# dyno_revA.net
KiCad netlist of a schematic drawn in EAGLE
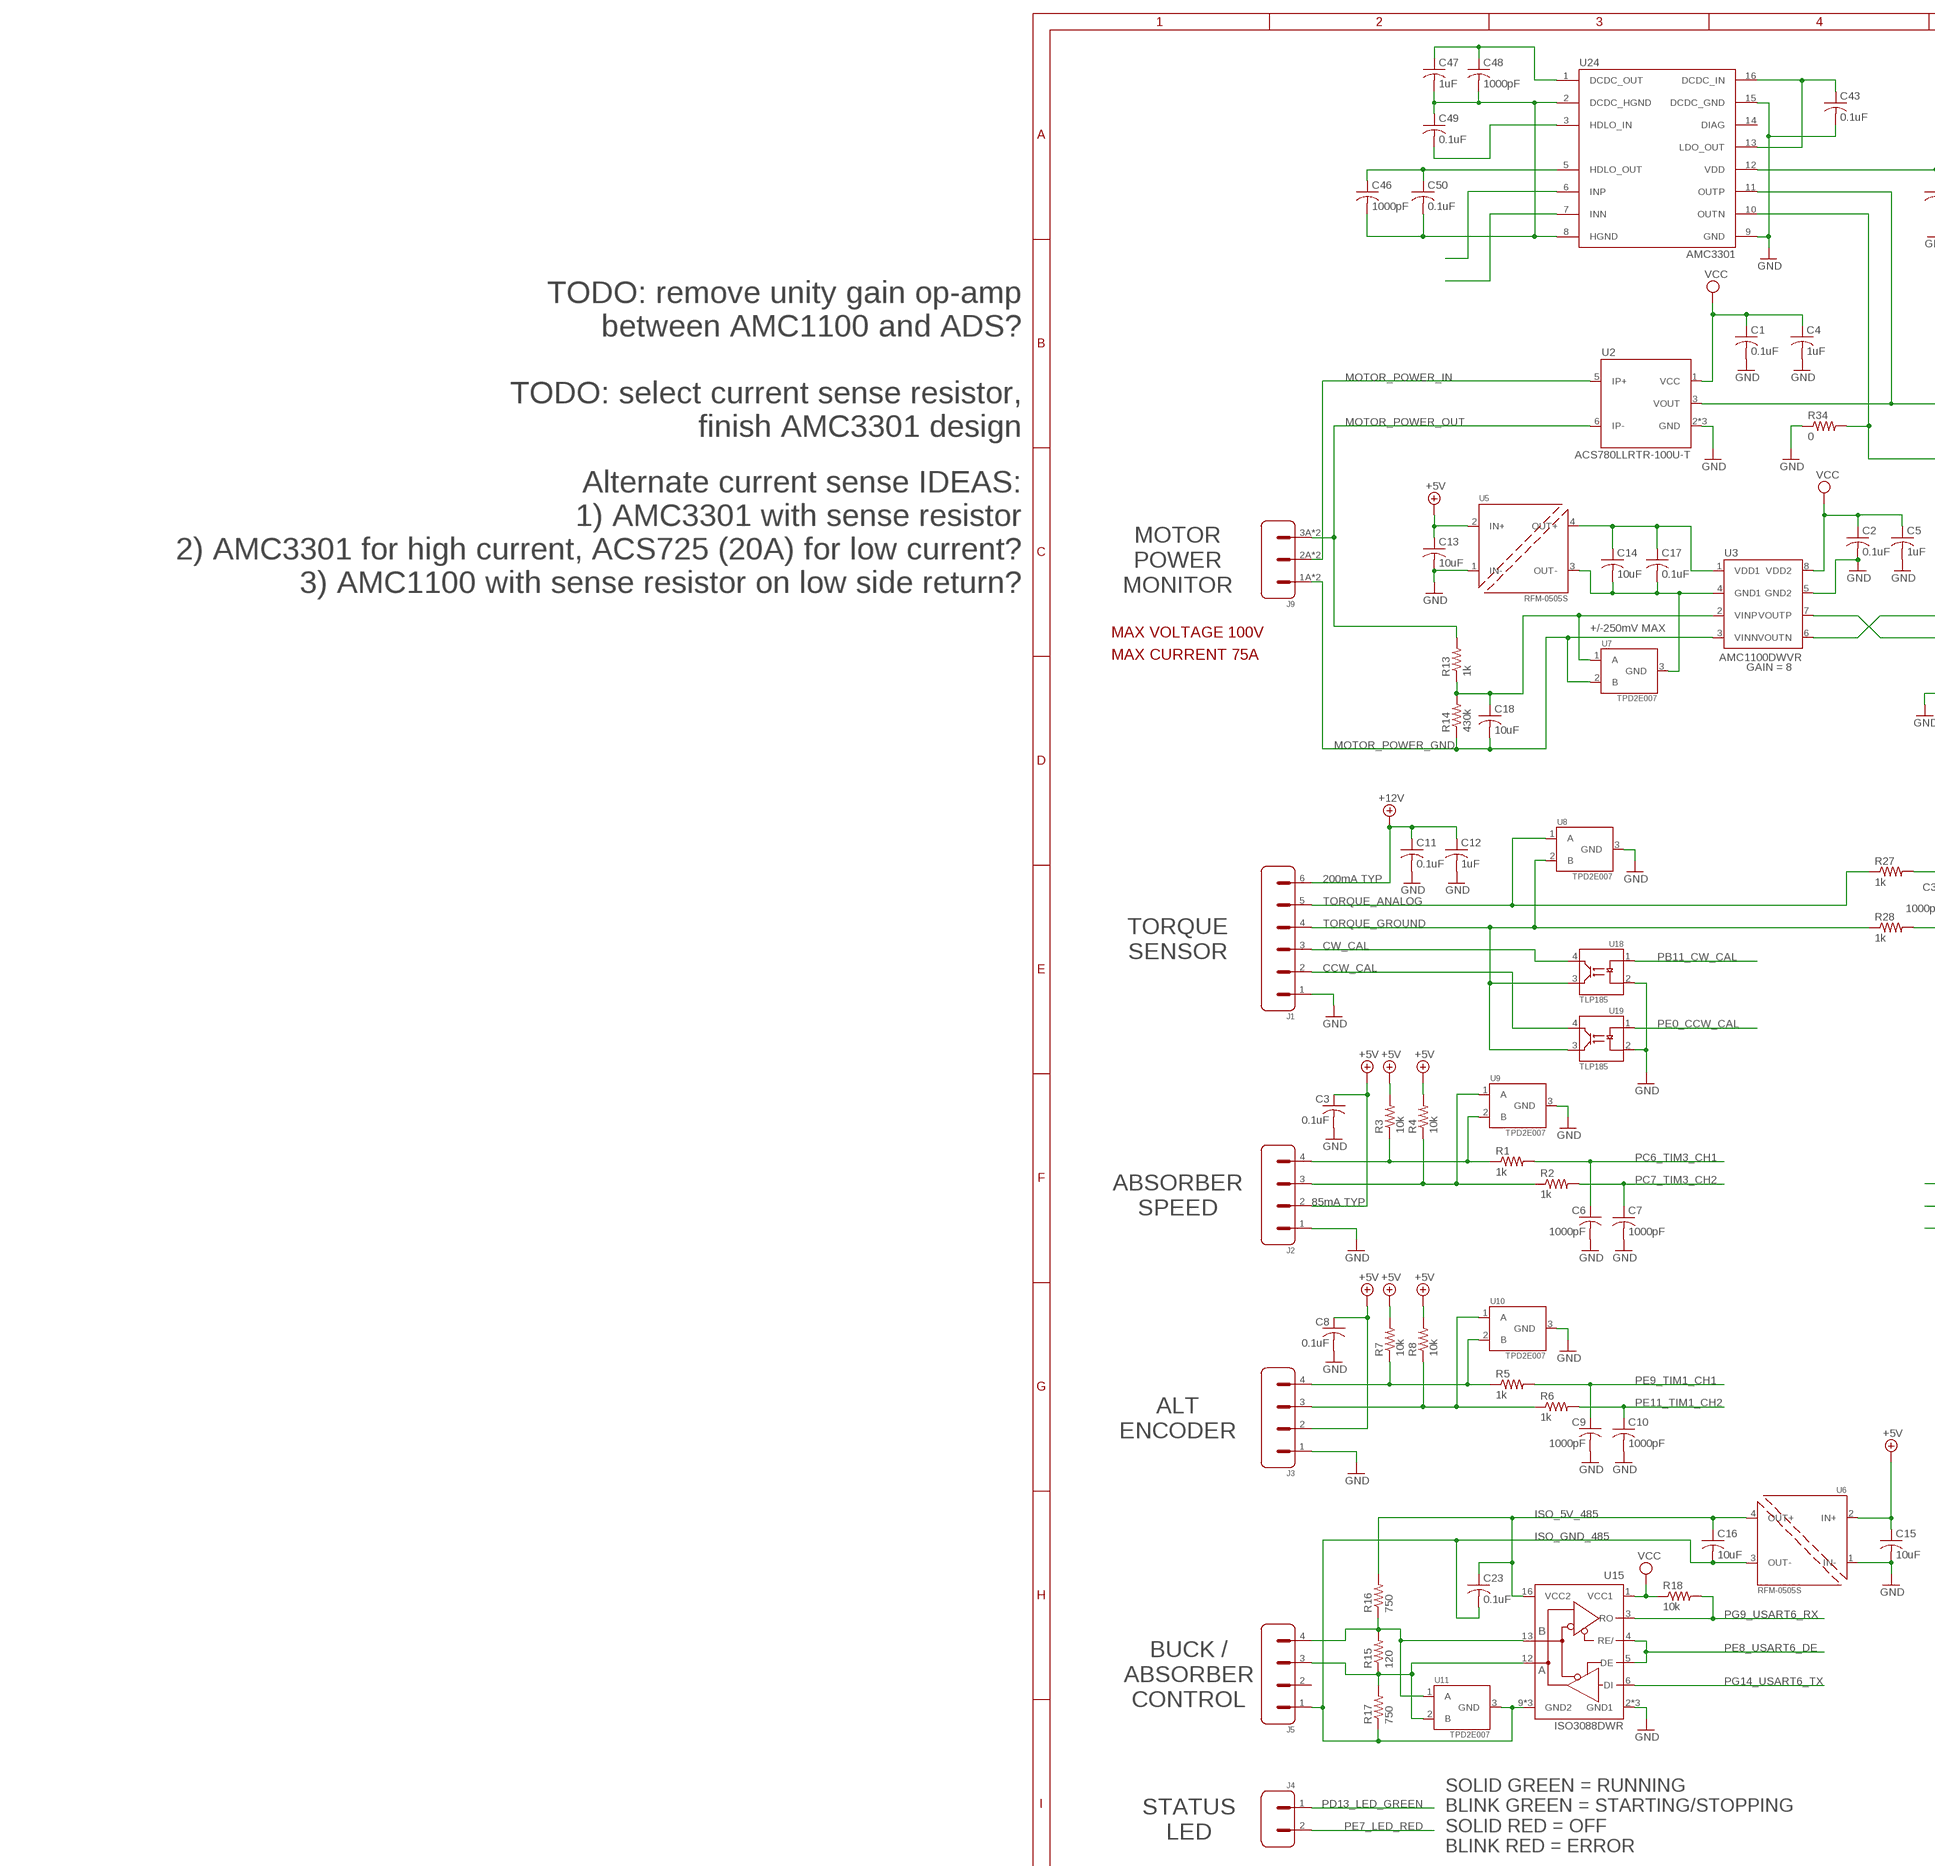
[diagram p0: schematic, sheet 1, part 1 of 2]
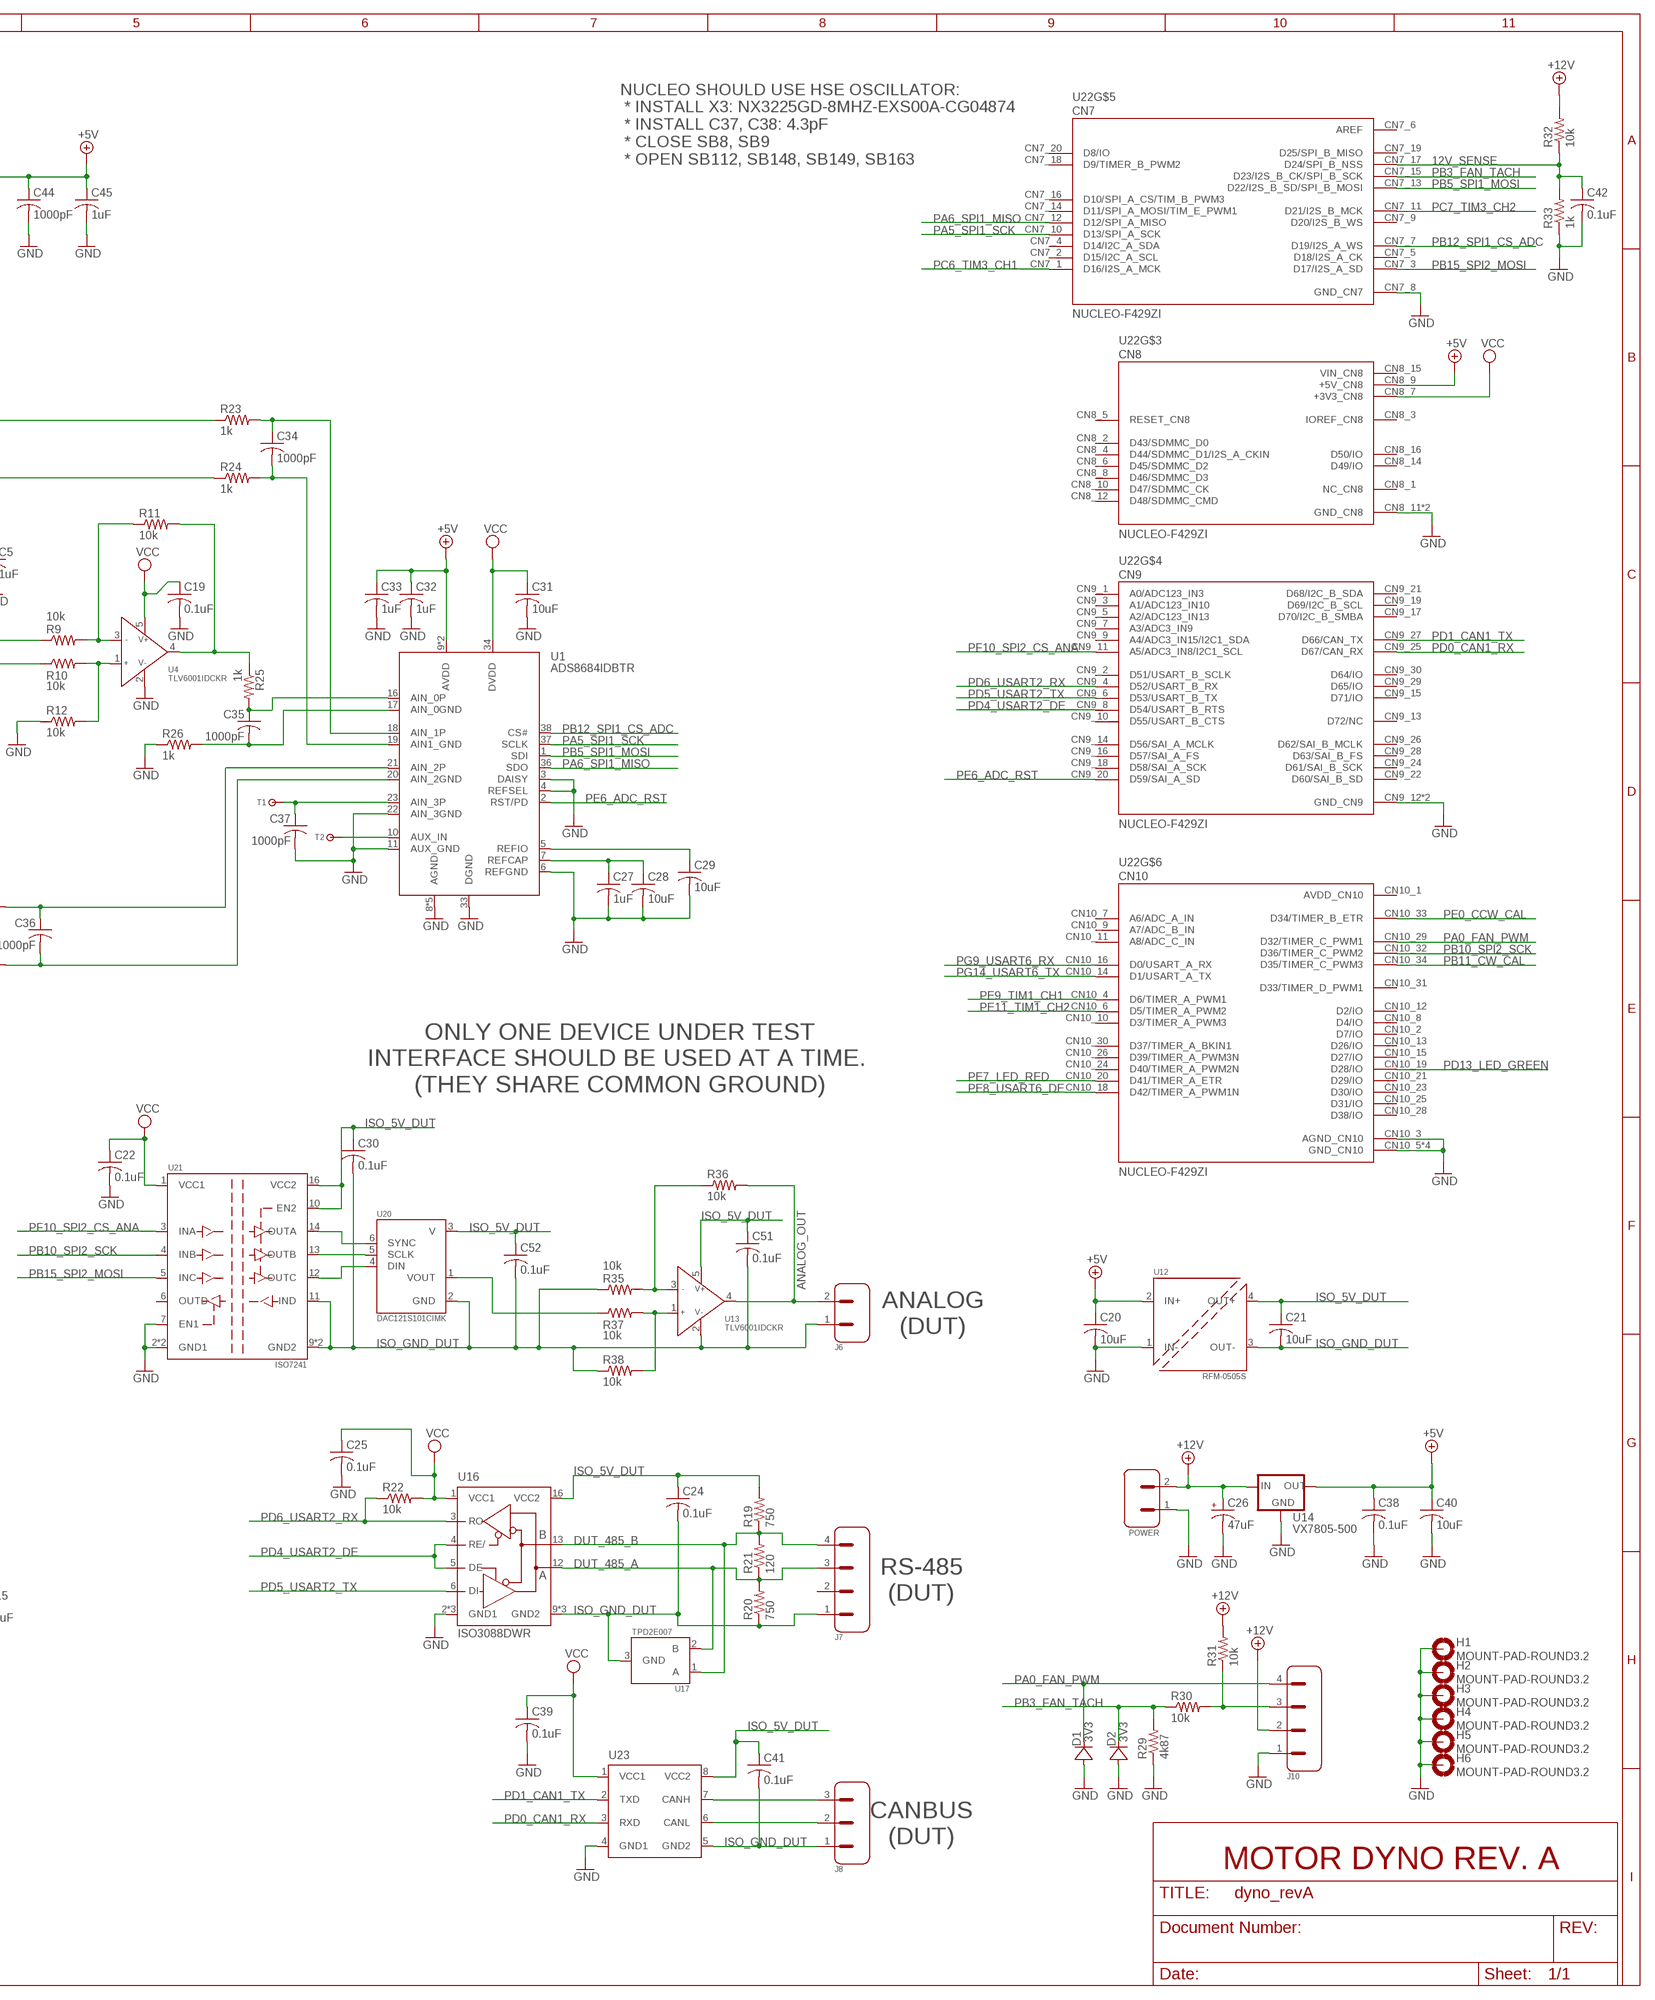
[diagram p1: schematic, sheet 1, part 2 of 2]

(export (version "E")
  (design (tool "Eeschema 10.0.6"))
  (components
    (comp (ref "C1")
      (value "0.1uF")
      (footprint "eagle-import:CAPC1608X90(C0603)")
      (fields (field (name "VOLTAGE") "50V"))
      (libsource (lib "eagle-import") (part "CL10B104KB8NNNC"))
    )
    (comp (ref "C2")
      (value "0.1uF")
      (footprint "eagle-import:CAPC1608X90(C0603)")
      (fields (field (name "VOLTAGE") "50V"))
      (libsource (lib "eagle-import") (part "CL10B104KB8NNNC"))
    )
    (comp (ref "C3")
      (value "0.1uF")
      (footprint "eagle-import:CAPC1608X90(C0603)")
      (fields (field (name "VOLTAGE") "50V"))
      (libsource (lib "eagle-import") (part "CL10B104KB8NNNC"))
    )
    (comp (ref "C4")
      (value "1uF")
      (footprint "eagle-import:CAPC1608X90(C0603)")
      (fields (field (name "VOLTAGE") "50V"))
      (libsource (lib "eagle-import") (part "CL10A105KB8NNNC"))
    )
    (comp (ref "C5")
      (value "1uF")
      (footprint "eagle-import:CAPC1608X90(C0603)")
      (fields (field (name "VOLTAGE") "50V"))
      (libsource (lib "eagle-import") (part "CL10A105KB8NNNC"))
    )
    (comp (ref "C6")
      (value "1000pF")
      (footprint "eagle-import:CAPC1608X90(C0603)")
      (fields (field (name "VOLTAGE") "50V"))
      (libsource (lib "eagle-import") (part "CL10B102KB8NNNC"))
    )
    (comp (ref "C7")
      (value "1000pF")
      (footprint "eagle-import:CAPC1608X90(C0603)")
      (fields (field (name "VOLTAGE") "50V"))
      (libsource (lib "eagle-import") (part "CL10B102KB8NNNC"))
    )
    (comp (ref "C8")
      (value "0.1uF")
      (footprint "eagle-import:CAPC1608X90(C0603)")
      (fields (field (name "VOLTAGE") "50V"))
      (libsource (lib "eagle-import") (part "CL10B104KB8NNNC"))
    )
    (comp (ref "C9")
      (value "1000pF")
      (footprint "eagle-import:CAPC1608X90(C0603)")
      (fields (field (name "VOLTAGE") "50V"))
      (libsource (lib "eagle-import") (part "CL10B102KB8NNNC"))
    )
    (comp (ref "C10")
      (value "1000pF")
      (footprint "eagle-import:CAPC1608X90(C0603)")
      (fields (field (name "VOLTAGE") "50V"))
      (libsource (lib "eagle-import") (part "CL10B102KB8NNNC"))
    )
    (comp (ref "C11")
      (value "0.1uF")
      (footprint "eagle-import:CAPC1608X90(C0603)")
      (fields (field (name "VOLTAGE") "50V"))
      (libsource (lib "eagle-import") (part "CL10B104KB8NNNC"))
    )
    (comp (ref "C12")
      (value "1uF")
      (footprint "eagle-import:CAPC1608X90(C0603)")
      (fields (field (name "VOLTAGE") "50V"))
      (libsource (lib "eagle-import") (part "CL10A105KB8NNNC"))
    )
    (comp (ref "C13")
      (value "10uF")
      (footprint "eagle-import:CAPC2012X145")
      (fields (field (name "VOLTAGE") "25V"))
      (libsource (lib "eagle-import") (part "CL21A106KAYNNNE"))
    )
    (comp (ref "C14")
      (value "10uF")
      (footprint "eagle-import:CAPC2012X145")
      (fields (field (name "VOLTAGE") "25V"))
      (libsource (lib "eagle-import") (part "CL21A106KAYNNNE"))
    )
    (comp (ref "C15")
      (value "10uF")
      (footprint "eagle-import:CAPC2012X145")
      (fields (field (name "VOLTAGE") "25V"))
      (libsource (lib "eagle-import") (part "CL21A106KAYNNNE"))
    )
    (comp (ref "C16")
      (value "10uF")
      (footprint "eagle-import:CAPC2012X145")
      (fields (field (name "VOLTAGE") "25V"))
      (libsource (lib "eagle-import") (part "CL21A106KAYNNNE"))
    )
    (comp (ref "C17")
      (value "0.1uF")
      (footprint "eagle-import:CAPC1608X90(C0603)")
      (fields (field (name "VOLTAGE") "50V"))
      (libsource (lib "eagle-import") (part "CL10B104KB8NNNC"))
    )
    (comp (ref "C18")
      (value "10uF")
      (footprint "eagle-import:CAPC2012X145")
      (fields (field (name "VOLTAGE") "25V"))
      (libsource (lib "eagle-import") (part "CL21A106KAYNNNE"))
    )
    (comp (ref "C19")
      (value "0.1uF")
      (footprint "eagle-import:CAPC1608X90(C0603)")
      (fields (field (name "VOLTAGE") "50V"))
      (libsource (lib "eagle-import") (part "CL10B104KB8NNNC"))
    )
    (comp (ref "C20")
      (value "10uF")
      (footprint "eagle-import:CAPC2012X145")
      (fields (field (name "VOLTAGE") "25V"))
      (libsource (lib "eagle-import") (part "CL21A106KAYNNNE"))
    )
    (comp (ref "C21")
      (value "10uF")
      (footprint "eagle-import:CAPC2012X145")
      (fields (field (name "VOLTAGE") "25V"))
      (libsource (lib "eagle-import") (part "CL21A106KAYNNNE"))
    )
    (comp (ref "C22")
      (value "0.1uF")
      (footprint "eagle-import:CAPC1608X90(C0603)")
      (fields (field (name "VOLTAGE") "50V"))
      (libsource (lib "eagle-import") (part "CL10B104KB8NNNC"))
    )
    (comp (ref "C23")
      (value "0.1uF")
      (footprint "eagle-import:CAPC1608X90(C0603)")
      (fields (field (name "VOLTAGE") "50V"))
      (libsource (lib "eagle-import") (part "CL10B104KB8NNNC"))
    )
    (comp (ref "C24")
      (value "0.1uF")
      (footprint "eagle-import:CAPC1608X90(C0603)")
      (fields (field (name "VOLTAGE") "50V"))
      (libsource (lib "eagle-import") (part "CL10B104KB8NNNC"))
    )
    (comp (ref "C25")
      (value "0.1uF")
      (footprint "eagle-import:CAPC1608X90(C0603)")
      (fields (field (name "VOLTAGE") "50V"))
      (libsource (lib "eagle-import") (part "CL10B104KB8NNNC"))
    )
    (comp (ref "C26")
      (value "47uF")
      (footprint "eagle-import:CAPAE830X850(PANA_F)")
      (libsource (lib "eagle-import") (part "HHXA500ARA470MHA0G"))
    )
    (comp (ref "C27")
      (value "1uF")
      (footprint "eagle-import:CAPC1608X90(C0603)")
      (fields (field (name "VOLTAGE") "50V"))
      (libsource (lib "eagle-import") (part "CL10A105KB8NNNC"))
    )
    (comp (ref "C28")
      (value "10uF")
      (footprint "eagle-import:CAPC1608X90(C0603)")
      (fields (field (name "VOLTAGE") "6.3V"))
      (libsource (lib "eagle-import") (part "CL10A106KQ8NNNC"))
    )
    (comp (ref "C29")
      (value "10uF")
      (footprint "eagle-import:CAPC1608X90(C0603)")
      (fields (field (name "VOLTAGE") "6.3V"))
      (libsource (lib "eagle-import") (part "CL10A106KQ8NNNC"))
    )
    (comp (ref "C30")
      (value "0.1uF")
      (footprint "eagle-import:CAPC1608X90(C0603)")
      (fields (field (name "VOLTAGE") "50V"))
      (libsource (lib "eagle-import") (part "CL10B104KB8NNNC"))
    )
    (comp (ref "C31")
      (value "10uF")
      (footprint "eagle-import:CAPC1608X90(C0603)")
      (fields (field (name "VOLTAGE") "6.3V"))
      (libsource (lib "eagle-import") (part "CL10A106KQ8NNNC"))
    )
    (comp (ref "C32")
      (value "1uF")
      (footprint "eagle-import:CAPC1608X90(C0603)")
      (fields (field (name "VOLTAGE") "50V"))
      (libsource (lib "eagle-import") (part "CL10A105KB8NNNC"))
    )
    (comp (ref "C33")
      (value "1uF")
      (footprint "eagle-import:CAPC1608X90(C0603)")
      (fields (field (name "VOLTAGE") "50V"))
      (libsource (lib "eagle-import") (part "CL10A105KB8NNNC"))
    )
    (comp (ref "C34")
      (value "1000pF")
      (footprint "eagle-import:CAPC1608X90(C0603)")
      (fields (field (name "VOLTAGE") "50V"))
      (libsource (lib "eagle-import") (part "CL10B102KB8NNNC"))
    )
    (comp (ref "C35")
      (value "1000pF")
      (footprint "eagle-import:CAPC1608X90(C0603)")
      (fields (field (name "VOLTAGE") "50V"))
      (libsource (lib "eagle-import") (part "CL10B102KB8NNNC"))
    )
    (comp (ref "C36")
      (value "1000pF")
      (footprint "eagle-import:CAPC1608X90(C0603)")
      (fields (field (name "VOLTAGE") "50V"))
      (libsource (lib "eagle-import") (part "CL10B102KB8NNNC"))
    )
    (comp (ref "C37")
      (value "1000pF")
      (footprint "eagle-import:CAPC1608X90(C0603)")
      (fields (field (name "VOLTAGE") "50V"))
      (libsource (lib "eagle-import") (part "CL10B102KB8NNNC"))
    )
    (comp (ref "C38")
      (value "0.1uF")
      (footprint "eagle-import:CAPC1608X90(C0603)")
      (fields (field (name "VOLTAGE") "50V"))
      (libsource (lib "eagle-import") (part "CL10B104KB8NNNC"))
    )
    (comp (ref "C39")
      (value "0.1uF")
      (footprint "eagle-import:CAPC1608X90(C0603)")
      (fields (field (name "VOLTAGE") "50V"))
      (libsource (lib "eagle-import") (part "CL10B104KB8NNNC"))
    )
    (comp (ref "C40")
      (value "10uF")
      (footprint "eagle-import:CAPC2012X145")
      (fields (field (name "VOLTAGE") "25V"))
      (libsource (lib "eagle-import") (part "CL21A106KAYNNNE"))
    )
    (comp (ref "C41")
      (value "0.1uF")
      (footprint "eagle-import:CAPC1608X90(C0603)")
      (fields (field (name "VOLTAGE") "50V"))
      (libsource (lib "eagle-import") (part "CL10B104KB8NNNC"))
    )
    (comp (ref "C42")
      (value "0.1uF")
      (footprint "eagle-import:CAPC1608X90(C0603)")
      (fields (field (name "VOLTAGE") "50V"))
      (libsource (lib "eagle-import") (part "CL10B104KB8NNNC"))
    )
    (comp (ref "C43")
      (value "0.1uF")
      (footprint "eagle-import:CAPC1608X90(C0603)")
      (fields (field (name "VOLTAGE") "50V"))
      (libsource (lib "eagle-import") (part "CL10B104KB8NNNC"))
    )
    (comp (ref "C44")
      (value "1000pF")
      (footprint "eagle-import:CAPC1608X90(C0603)")
      (fields (field (name "VOLTAGE") "50V"))
      (libsource (lib "eagle-import") (part "CL10B102KB8NNNC"))
    )
    (comp (ref "C45")
      (value "1uF")
      (footprint "eagle-import:CAPC1608X90(C0603)")
      (fields (field (name "VOLTAGE") "50V"))
      (libsource (lib "eagle-import") (part "CL10A105KB8NNNC"))
    )
    (comp (ref "C46")
      (value "1000pF")
      (footprint "eagle-import:CAPC1608X90(C0603)")
      (fields (field (name "VOLTAGE") "50V"))
      (libsource (lib "eagle-import") (part "CL10B102KB8NNNC"))
    )
    (comp (ref "C47")
      (value "1uF")
      (footprint "eagle-import:CAPC1608X90(C0603)")
      (fields (field (name "VOLTAGE") "50V"))
      (libsource (lib "eagle-import") (part "CL10A105KB8NNNC"))
    )
    (comp (ref "C48")
      (value "1000pF")
      (footprint "eagle-import:CAPC1608X90(C0603)")
      (fields (field (name "VOLTAGE") "50V"))
      (libsource (lib "eagle-import") (part "CL10B102KB8NNNC"))
    )
    (comp (ref "C49")
      (value "0.1uF")
      (footprint "eagle-import:CAPC1608X90(C0603)")
      (fields (field (name "VOLTAGE") "50V"))
      (libsource (lib "eagle-import") (part "CL10B104KB8NNNC"))
    )
    (comp (ref "C50")
      (value "0.1uF")
      (footprint "eagle-import:CAPC1608X90(C0603)")
      (fields (field (name "VOLTAGE") "50V"))
      (libsource (lib "eagle-import") (part "CL10B104KB8NNNC"))
    )
    (comp (ref "C51")
      (value "0.1uF")
      (footprint "eagle-import:CAPC1608X90(C0603)")
      (fields (field (name "VOLTAGE") "50V"))
      (libsource (lib "eagle-import") (part "CL10B104KB8NNNC"))
    )
    (comp (ref "C52")
      (value "0.1uF")
      (footprint "eagle-import:CAPC1608X90(C0603)")
      (fields (field (name "VOLTAGE") "50V"))
      (libsource (lib "eagle-import") (part "CL10B104KB8NNNC"))
    )
    (comp (ref "D1")
      (value "3V3")
      (footprint "eagle-import:SOD2513X110(SOD323)")
      (libsource (lib "eagle-import") (part "D1213A-01WS-7"))
    )
    (comp (ref "D2")
      (value "3V3")
      (footprint "eagle-import:SOD2513X110(SOD323)")
      (libsource (lib "eagle-import") (part "D1213A-01WS-7"))
    )
    (comp (ref "H1")
      (value "MOUNT-PAD-ROUND3.2")
      (footprint "eagle-import:3,2-PAD")
      (libsource (lib "eagle-import") (part "MOUNT-PAD-ROUND3.2"))
    )
    (comp (ref "H2")
      (value "MOUNT-PAD-ROUND3.2")
      (footprint "eagle-import:3,2-PAD")
      (libsource (lib "eagle-import") (part "MOUNT-PAD-ROUND3.2"))
    )
    (comp (ref "H3")
      (value "MOUNT-PAD-ROUND3.2")
      (footprint "eagle-import:3,2-PAD")
      (libsource (lib "eagle-import") (part "MOUNT-PAD-ROUND3.2"))
    )
    (comp (ref "H4")
      (value "MOUNT-PAD-ROUND3.2")
      (footprint "eagle-import:3,2-PAD")
      (libsource (lib "eagle-import") (part "MOUNT-PAD-ROUND3.2"))
    )
    (comp (ref "H5")
      (value "MOUNT-PAD-ROUND3.2")
      (footprint "eagle-import:3,2-PAD")
      (libsource (lib "eagle-import") (part "MOUNT-PAD-ROUND3.2"))
    )
    (comp (ref "H6")
      (value "MOUNT-PAD-ROUND3.2")
      (footprint "eagle-import:3,2-PAD")
      (libsource (lib "eagle-import") (part "MOUNT-PAD-ROUND3.2"))
    )
    (comp (ref "J1")
      (value "502584-0670")
      (footprint "eagle-import:502584-0670")
      (libsource (lib "eagle-import") (part "502584-0670"))
    )
    (comp (ref "J2")
      (value "502584-0470")
      (footprint "eagle-import:502584-0470")
      (libsource (lib "eagle-import") (part "502584-0470"))
    )
    (comp (ref "J3")
      (value "502584-0470")
      (footprint "eagle-import:502584-0470")
      (libsource (lib "eagle-import") (part "502584-0470"))
    )
    (comp (ref "J4")
      (value "502584-0270")
      (footprint "eagle-import:502584-0270")
      (libsource (lib "eagle-import") (part "502584-0270"))
    )
    (comp (ref "J5")
      (value "43650-0416")
      (footprint "eagle-import:43650-0416")
      (libsource (lib "eagle-import") (part "43650-0416"))
    )
    (comp (ref "J6")
      (value "502584-0270")
      (footprint "eagle-import:502584-0270")
      (libsource (lib "eagle-import") (part "502584-0270"))
    )
    (comp (ref "J7")
      (value "43650-0416")
      (footprint "eagle-import:43650-0416")
      (libsource (lib "eagle-import") (part "43650-0416"))
    )
    (comp (ref "J8")
      (value "43650-0316")
      (footprint "eagle-import:43650-0316")
      (libsource (lib "eagle-import") (part "43650-0316"))
    )
    (comp (ref "J9")
      (value "1017532")
      (footprint "eagle-import:1017532")
      (libsource (lib "eagle-import") (part "1017532"))
    )
    (comp (ref "J10")
      (value "22-23-2041")
      (footprint "eagle-import:22-23-2041")
      (libsource (lib "eagle-import") (part "22-23-2041"))
    )
    (comp (ref "POWER")
      (value "39-29-0023")
      (footprint "eagle-import:5566-2")
      (libsource (lib "eagle-import") (part "39-29-0023"))
    )
    (comp (ref "R1")
      (value "1k")
      (footprint "eagle-import:RESC1608X55(ERJ-0603)")
      (libsource (lib "eagle-import") (part "ERJ-3EKF1001V"))
    )
    (comp (ref "R2")
      (value "1k")
      (footprint "eagle-import:RESC1608X55(ERJ-0603)")
      (libsource (lib "eagle-import") (part "ERJ-3EKF1001V"))
    )
    (comp (ref "R3")
      (value "10k")
      (footprint "eagle-import:RESC1608X55(ERJ-0603)")
      (libsource (lib "eagle-import") (part "ERJ-3EKF1002V"))
    )
    (comp (ref "R4")
      (value "10k")
      (footprint "eagle-import:RESC1608X55(ERJ-0603)")
      (libsource (lib "eagle-import") (part "ERJ-3EKF1002V"))
    )
    (comp (ref "R5")
      (value "1k")
      (footprint "eagle-import:RESC1608X55(ERJ-0603)")
      (libsource (lib "eagle-import") (part "ERJ-3EKF1001V"))
    )
    (comp (ref "R6")
      (value "1k")
      (footprint "eagle-import:RESC1608X55(ERJ-0603)")
      (libsource (lib "eagle-import") (part "ERJ-3EKF1001V"))
    )
    (comp (ref "R7")
      (value "10k")
      (footprint "eagle-import:RESC1608X55(ERJ-0603)")
      (libsource (lib "eagle-import") (part "ERJ-3EKF1002V"))
    )
    (comp (ref "R8")
      (value "10k")
      (footprint "eagle-import:RESC1608X55(ERJ-0603)")
      (libsource (lib "eagle-import") (part "ERJ-3EKF1002V"))
    )
    (comp (ref "R9")
      (value "10k")
      (footprint "eagle-import:RESC1608X55(ERJ-0603)")
      (libsource (lib "eagle-import") (part "ERJ-3EKF1002V"))
    )
    (comp (ref "R10")
      (value "10k")
      (footprint "eagle-import:RESC1608X55(ERJ-0603)")
      (libsource (lib "eagle-import") (part "ERJ-3EKF1002V"))
    )
    (comp (ref "R11")
      (value "10k")
      (footprint "eagle-import:RESC1608X55(ERJ-0603)")
      (libsource (lib "eagle-import") (part "ERJ-3EKF1002V"))
    )
    (comp (ref "R12")
      (value "10k")
      (footprint "eagle-import:RESC1608X55(ERJ-0603)")
      (libsource (lib "eagle-import") (part "ERJ-3EKF1002V"))
    )
    (comp (ref "R13")
      (value "1k")
      (footprint "eagle-import:RESC1608X55(ERJ-0603)")
      (libsource (lib "eagle-import") (part "ERJ-3EKF1001V"))
    )
    (comp (ref "R14")
      (value "430k")
      (footprint "eagle-import:RESC1608X55(ERJ-0603)")
      (libsource (lib "eagle-import") (part "ERJ-3EKF4303V"))
    )
    (comp (ref "R15")
      (value "120")
      (footprint "eagle-import:RESC1608X55(ERJ-0603)")
      (libsource (lib "eagle-import") (part "ERJ-3EKF1200V"))
    )
    (comp (ref "R16")
      (value "750")
      (footprint "eagle-import:RESC1608X55(ERJ-0603)")
      (libsource (lib "eagle-import") (part "ERJ-3EKF7500V"))
    )
    (comp (ref "R17")
      (value "750")
      (footprint "eagle-import:RESC1608X55(ERJ-0603)")
      (libsource (lib "eagle-import") (part "ERJ-3EKF7500V"))
    )
    (comp (ref "R18")
      (value "10k")
      (footprint "eagle-import:RESC1608X55(ERJ-0603)")
      (libsource (lib "eagle-import") (part "ERJ-3EKF1002V"))
    )
    (comp (ref "R19")
      (value "750")
      (footprint "eagle-import:RESC1608X55(ERJ-0603)")
      (libsource (lib "eagle-import") (part "ERJ-3EKF7500V"))
    )
    (comp (ref "R20")
      (value "750")
      (footprint "eagle-import:RESC1608X55(ERJ-0603)")
      (libsource (lib "eagle-import") (part "ERJ-3EKF7500V"))
    )
    (comp (ref "R21")
      (value "120")
      (footprint "eagle-import:RESC1608X55(ERJ-0603)")
      (libsource (lib "eagle-import") (part "ERJ-3EKF1200V"))
    )
    (comp (ref "R22")
      (value "10k")
      (footprint "eagle-import:RESC1608X55(ERJ-0603)")
      (libsource (lib "eagle-import") (part "ERJ-3EKF1002V"))
    )
    (comp (ref "R23")
      (value "1k")
      (footprint "eagle-import:RESC1608X55(ERJ-0603)")
      (libsource (lib "eagle-import") (part "ERJ-3EKF1001V"))
    )
    (comp (ref "R24")
      (value "1k")
      (footprint "eagle-import:RESC1608X55(ERJ-0603)")
      (libsource (lib "eagle-import") (part "ERJ-3EKF1001V"))
    )
    (comp (ref "R25")
      (value "1k")
      (footprint "eagle-import:RESC1608X55(ERJ-0603)")
      (libsource (lib "eagle-import") (part "ERJ-3EKF1001V"))
    )
    (comp (ref "R26")
      (value "1k")
      (footprint "eagle-import:RESC1608X55(ERJ-0603)")
      (libsource (lib "eagle-import") (part "ERJ-3EKF1001V"))
    )
    (comp (ref "R27")
      (value "1k")
      (footprint "eagle-import:RESC1608X55(ERJ-0603)")
      (libsource (lib "eagle-import") (part "ERJ-3EKF1001V"))
    )
    (comp (ref "R28")
      (value "1k")
      (footprint "eagle-import:RESC1608X55(ERJ-0603)")
      (libsource (lib "eagle-import") (part "ERJ-3EKF1001V"))
    )
    (comp (ref "R29")
      (value "4k87")
      (footprint "eagle-import:RESC1608X55(ERJ-0603)")
      (libsource (lib "eagle-import") (part "ERJ-3EKF4871V"))
    )
    (comp (ref "R30")
      (value "10k")
      (footprint "eagle-import:RESC1608X55(ERJ-0603)")
      (libsource (lib "eagle-import") (part "ERJ-3EKF1002V"))
    )
    (comp (ref "R31")
      (value "10k")
      (footprint "eagle-import:RESC1608X55(ERJ-0603)")
      (libsource (lib "eagle-import") (part "ERJ-3EKF1002V"))
    )
    (comp (ref "R32")
      (value "10k")
      (footprint "eagle-import:RESC1608X55(ERJ-0603)")
      (libsource (lib "eagle-import") (part "ERJ-3EKF1002V"))
    )
    (comp (ref "R33")
      (value "1k")
      (footprint "eagle-import:RESC1608X55(ERJ-0603)")
      (libsource (lib "eagle-import") (part "ERJ-3EKF1001V"))
    )
    (comp (ref "R34")
      (value "0")
      (footprint "eagle-import:RESC1608X55(ERJ-0603)")
      (libsource (lib "eagle-import") (part "ERJ-S030"))
    )
    (comp (ref "R35")
      (value "10k")
      (footprint "eagle-import:RESC1608X55(ERJ-0603)")
      (libsource (lib "eagle-import") (part "ERJ-3EKF1002V"))
    )
    (comp (ref "R36")
      (value "10k")
      (footprint "eagle-import:RESC1608X55(ERJ-0603)")
      (libsource (lib "eagle-import") (part "ERJ-3EKF1002V"))
    )
    (comp (ref "R37")
      (value "10k")
      (footprint "eagle-import:RESC1608X55(ERJ-0603)")
      (libsource (lib "eagle-import") (part "ERJ-3EKF1002V"))
    )
    (comp (ref "R38")
      (value "10k")
      (footprint "eagle-import:RESC1608X55(ERJ-0603)")
      (libsource (lib "eagle-import") (part "ERJ-3EKF1002V"))
    )
    (comp (ref "T1")
      (value "TESTPAD")
      (footprint "eagle-import:TEST")
      (libsource (lib "eagle-import") (part "TESTPAD"))
    )
    (comp (ref "T2")
      (value "TESTPAD")
      (footprint "eagle-import:TEST")
      (libsource (lib "eagle-import") (part "TESTPAD"))
    )
    (comp (ref "U1")
      (value "ADS8684IDBTR")
      (footprint "eagle-import:SOP50P640X120-38")
      (libsource (lib "eagle-import") (part "ADS8684IDBTR"))
    )
    (comp (ref "U2")
      (value "ACS780LLRTR-100U-T")
      (footprint "eagle-import:ACS780")
      (libsource (lib "eagle-import") (part "ACS780LLRTR-100U-T"))
    )
    (comp (ref "U3")
      (value "AMC1100DWVR")
      (footprint "eagle-import:SOIC127P1150X280-8")
      (libsource (lib "eagle-import") (part "AMC1100DWVR"))
    )
    (comp (ref "U4")
      (value "TLV6001IDCKR")
      (footprint "eagle-import:SOT65P210X110-5")
      (libsource (lib "eagle-import") (part "TLV6001IDCKR"))
    )
    (comp (ref "U5")
      (value "RFM-0505S")
      (footprint "eagle-import:RFM")
      (libsource (lib "eagle-import") (part "RFM-0505S"))
    )
    (comp (ref "U6")
      (value "RFM-0505S")
      (footprint "eagle-import:RFM")
      (libsource (lib "eagle-import") (part "RFM-0505S"))
    )
    (comp (ref "U7")
      (value "TPD2E007")
      (footprint "eagle-import:SOT65P210X110-3(SOT323)")
      (libsource (lib "eagle-import") (part "TPD2E007"))
    )
    (comp (ref "U8")
      (value "TPD2E007")
      (footprint "eagle-import:SOT65P210X110-3(SOT323)")
      (libsource (lib "eagle-import") (part "TPD2E007"))
    )
    (comp (ref "U9")
      (value "TPD2E007")
      (footprint "eagle-import:SOT65P210X110-3(SOT323)")
      (libsource (lib "eagle-import") (part "TPD2E007"))
    )
    (comp (ref "U10")
      (value "TPD2E007")
      (footprint "eagle-import:SOT65P210X110-3(SOT323)")
      (libsource (lib "eagle-import") (part "TPD2E007"))
    )
    (comp (ref "U11")
      (value "TPD2E007")
      (footprint "eagle-import:SOT65P210X110-3(SOT323)")
      (libsource (lib "eagle-import") (part "TPD2E007"))
    )
    (comp (ref "U12")
      (value "RFM-0505S")
      (footprint "eagle-import:RFM")
      (libsource (lib "eagle-import") (part "RFM-0505S"))
    )
    (comp (ref "U13")
      (value "TLV6001IDCKR")
      (footprint "eagle-import:SOT65P210X110-5")
      (libsource (lib "eagle-import") (part "TLV6001IDCKR"))
    )
    (comp (ref "U14")
      (value "VX7805-500")
      (footprint "eagle-import:VX78-500")
      (libsource (lib "eagle-import") (part "VX7805-500"))
    )
    (comp (ref "U15")
      (value "ISO3088DWR")
      (footprint "eagle-import:SOIC127P1030X265-16")
      (libsource (lib "eagle-import") (part "ISO3088DWR"))
    )
    (comp (ref "U16")
      (value "ISO3088DWR")
      (footprint "eagle-import:SOIC127P1030X265-16")
      (libsource (lib "eagle-import") (part "ISO3088DWR"))
    )
    (comp (ref "U17")
      (value "TPD2E007")
      (footprint "eagle-import:SOT65P210X110-3(SOT323)")
      (libsource (lib "eagle-import") (part "TPD2E007"))
    )
    (comp (ref "U18")
      (value "TLP185")
      (footprint "eagle-import:SOT127P700X220-4")
      (libsource (lib "eagle-import") (part "TLP185"))
    )
    (comp (ref "U19")
      (value "TLP185")
      (footprint "eagle-import:SOT127P700X220-4")
      (libsource (lib "eagle-import") (part "TLP185"))
    )
    (comp (ref "U20")
      (value "DAC121S101CIMK")
      (footprint "eagle-import:SOT95P280X110-6")
      (libsource (lib "eagle-import") (part "DAC121S101CIMK"))
    )
    (comp (ref "U21")
      (value "ISO7241")
      (footprint "eagle-import:SOIC127P1030X265-16")
      (libsource (lib "eagle-import") (part "ISO7241"))
    )
    (comp (ref "U22")
      (value "NUCLEO-F429ZI")
      (footprint "eagle-import:MODULE_NUCLEO-F429ZI")
      (fields (field (name "MF") "STMicroelectronics"))
      (libsource (lib "eagle-import") (part "NUCLEO-F429ZI"))
    )
    (comp (ref "U23")
      (value "ISO1042DWVR")
      (footprint "eagle-import:SOIC127P1150X265-8N")
      (libsource (lib "eagle-import") (part "ISO1042DWVR"))
    )
    (comp (ref "U24")
      (value "AMC3301")
      (footprint "eagle-import:SOIC127P1030X265-16N")
      (libsource (lib "eagle-import") (part "AMC3301"))
    )
  )
  (nets
    (net (code "1") (name "+5V") (class "Default")
      (node (ref "C13") (pin "1") (pinfunction "1_1") (pintype "passive"))
      (node (ref "C15") (pin "1") (pinfunction "1_1") (pintype "passive"))
      (node (ref "C20") (pin "1") (pinfunction "1_1") (pintype "passive"))
      (node (ref "C3") (pin "1") (pinfunction "1_1") (pintype "passive"))
      (node (ref "C32") (pin "1") (pinfunction "1_1") (pintype "passive"))
      (node (ref "C33") (pin "1") (pinfunction "1_1") (pintype "passive"))
      (node (ref "C38") (pin "1") (pinfunction "1_1") (pintype "passive"))
      (node (ref "C40") (pin "1") (pinfunction "1_1") (pintype "passive"))
      (node (ref "C44") (pin "1") (pinfunction "1_1") (pintype "passive"))
      (node (ref "C45") (pin "1") (pinfunction "1_1") (pintype "passive"))
      (node (ref "C8") (pin "1") (pinfunction "1_1") (pintype "passive"))
      (node (ref "J2") (pin "2") (pinfunction "2_2") (pintype "bidirectional"))
      (node (ref "J3") (pin "2") (pinfunction "2_2") (pintype "bidirectional"))
      (node (ref "R3") (pin "2") (pinfunction "2_2") (pintype "passive"))
      (node (ref "R4") (pin "2") (pinfunction "2_2") (pintype "passive"))
      (node (ref "R7") (pin "2") (pinfunction "2_2") (pintype "passive"))
      (node (ref "R8") (pin "2") (pinfunction "2_2") (pintype "passive"))
      (node (ref "U1") (pin "30") (pinfunction "AVDD_30") (pintype "bidirectional"))
      (node (ref "U1") (pin "9") (pinfunction "AVDD_9") (pintype "bidirectional"))
      (node (ref "U12") (pin "2") (pinfunction "IN+_2") (pintype "bidirectional"))
      (node (ref "U14") (pin "3") (pinfunction "OUT_3") (pintype "passive"))
      (node (ref "U22") (pin "CN8_9") (pinfunction "+5V_CN8_CN8_9") (pintype "power_in"))
      (node (ref "U24") (pin "12") (pinfunction "VDD_12") (pintype "bidirectional"))
      (node (ref "U5") (pin "2") (pinfunction "IN+_2") (pintype "bidirectional"))
      (node (ref "U6") (pin "2") (pinfunction "IN+_2") (pintype "bidirectional"))
    )
    (net (code "2") (name "+12V") (class "Default")
      (node (ref "C11") (pin "1") (pinfunction "1_1") (pintype "passive"))
      (node (ref "C12") (pin "1") (pinfunction "1_1") (pintype "passive"))
      (node (ref "C26") (pin "1") (pinfunction "+_1") (pintype "passive"))
      (node (ref "J1") (pin "6") (pinfunction "6_6") (pintype "bidirectional"))
      (node (ref "J10") (pin "2") (pinfunction "2_2") (pintype "bidirectional"))
      (node (ref "POWER") (pin "2") (pinfunction "2_2") (pintype "bidirectional"))
      (node (ref "R31") (pin "2") (pinfunction "2_2") (pintype "passive"))
      (node (ref "R32") (pin "2") (pinfunction "2_2") (pintype "passive"))
      (node (ref "U14") (pin "1") (pinfunction "IN_1") (pintype "input"))
    )
    (net (code "3") (name "/12V_SENSE") (class "Default")
      (node (ref "C42") (pin "1") (pinfunction "1_1") (pintype "passive"))
      (node (ref "R32") (pin "1") (pinfunction "1_1") (pintype "passive"))
      (node (ref "R33") (pin "2") (pinfunction "2_2") (pintype "passive"))
      (node (ref "U22") (pin "CN7_17") (pinfunction "D24/SPI_B_NSS_CN7_17") (pintype "bidirectional"))
    )
    (net (code "4") (name "/ANALOG_OUT") (class "Default")
      (node (ref "J6") (pin "2") (pinfunction "2_2") (pintype "bidirectional"))
      (node (ref "R36") (pin "2") (pinfunction "2_2") (pintype "passive"))
      (node (ref "U13") (pin "4") (pinfunction "OUT_4") (pintype "bidirectional"))
    )
    (net (code "5") (name "/AREF") (class "Default")
      (node (ref "U22") (pin "CN7_6") (pinfunction "AREF_CN7_6") (pintype "power_in"))
    )
    (net (code "6") (name "/AVDD_CN10") (class "Default")
      (node (ref "U22") (pin "CN10_1") (pinfunction "AVDD_CN10_CN10_1") (pintype "power_in"))
    )
    (net (code "7") (name "/CCW_CAL") (class "Default")
      (node (ref "J1") (pin "2") (pinfunction "2_2") (pintype "bidirectional"))
      (node (ref "U19") (pin "4") (pinfunction "COLL_4") (pintype "bidirectional"))
    )
    (net (code "8") (name "/CW_CAL") (class "Default")
      (node (ref "J1") (pin "3") (pinfunction "3_3") (pintype "bidirectional"))
      (node (ref "U18") (pin "4") (pinfunction "COLL_4") (pintype "bidirectional"))
    )
    (net (code "9") (name "/DUT_485_A") (class "Default")
      (node (ref "J7") (pin "3") (pinfunction "3_3") (pintype "bidirectional"))
      (node (ref "R20") (pin "2") (pinfunction "2_2") (pintype "passive"))
      (node (ref "R21") (pin "1") (pinfunction "1_1") (pintype "passive"))
      (node (ref "U16") (pin "12") (pinfunction "A_12") (pintype "passive"))
      (node (ref "U17") (pin "2") (pinfunction "B_2") (pintype "bidirectional"))
    )
    (net (code "10") (name "/DUT_485_B") (class "Default")
      (node (ref "J7") (pin "4") (pinfunction "4_4") (pintype "bidirectional"))
      (node (ref "R19") (pin "1") (pinfunction "1_1") (pintype "passive"))
      (node (ref "R21") (pin "2") (pinfunction "2_2") (pintype "passive"))
      (node (ref "U16") (pin "13") (pinfunction "B_13") (pintype "passive"))
      (node (ref "U17") (pin "1") (pinfunction "A_1") (pintype "bidirectional"))
    )
    (net (code "11") (name "/ISO_5V_485") (class "Default")
      (node (ref "C16") (pin "1") (pinfunction "1_1") (pintype "passive"))
      (node (ref "C23") (pin "1") (pinfunction "1_1") (pintype "passive"))
      (node (ref "R16") (pin "2") (pinfunction "2_2") (pintype "passive"))
      (node (ref "U15") (pin "16") (pinfunction "VCC2_16") (pintype "bidirectional"))
      (node (ref "U6") (pin "4") (pinfunction "OUT+_4") (pintype "bidirectional"))
    )
    (net (code "12") (name "/ISO_5V_DUT") (class "Default")
      (node (ref "C21") (pin "1") (pinfunction "1_1") (pintype "passive"))
      (node (ref "C24") (pin "1") (pinfunction "1_1") (pintype "passive"))
      (node (ref "C30") (pin "1") (pinfunction "1_1") (pintype "passive"))
      (node (ref "C41") (pin "1") (pinfunction "1_1") (pintype "passive"))
      (node (ref "C51") (pin "1") (pinfunction "1_1") (pintype "passive"))
      (node (ref "C52") (pin "1") (pinfunction "1_1") (pintype "passive"))
      (node (ref "R19") (pin "2") (pinfunction "2_2") (pintype "passive"))
      (node (ref "U12") (pin "4") (pinfunction "OUT+_4") (pintype "bidirectional"))
      (node (ref "U13") (pin "5") (pinfunction "V+_5") (pintype "bidirectional"))
      (node (ref "U16") (pin "16") (pinfunction "VCC2_16") (pintype "bidirectional"))
      (node (ref "U20") (pin "3") (pinfunction "V_3") (pintype "bidirectional"))
      (node (ref "U21") (pin "10") (pinfunction "EN2_10") (pintype "bidirectional"))
      (node (ref "U21") (pin "16") (pinfunction "VCC2_16") (pintype "bidirectional"))
      (node (ref "U23") (pin "8") (pinfunction "VCC2_8") (pintype "bidirectional"))
    )
    (net (code "13") (name "/ISO_GND_485") (class "Default")
      (node (ref "C16") (pin "2") (pinfunction "2_2") (pintype "passive"))
      (node (ref "C23") (pin "2") (pinfunction "2_2") (pintype "passive"))
      (node (ref "J5") (pin "1") (pinfunction "1_1") (pintype "bidirectional"))
      (node (ref "R17") (pin "1") (pinfunction "1_1") (pintype "passive"))
      (node (ref "U11") (pin "3") (pinfunction "GND_3") (pintype "bidirectional"))
      (node (ref "U15") (pin "10") (pinfunction "GND2_10") (pintype "bidirectional"))
      (node (ref "U15") (pin "15") (pinfunction "GND2_15") (pintype "bidirectional"))
      (node (ref "U15") (pin "9") (pinfunction "GND2_9") (pintype "bidirectional"))
      (node (ref "U6") (pin "3") (pinfunction "OUT-_3") (pintype "bidirectional"))
    )
    (net (code "14") (name "/ISO_GND_DUT") (class "Default")
      (node (ref "C21") (pin "2") (pinfunction "2_2") (pintype "passive"))
      (node (ref "C24") (pin "2") (pinfunction "2_2") (pintype "passive"))
      (node (ref "C30") (pin "2") (pinfunction "2_2") (pintype "passive"))
      (node (ref "C41") (pin "2") (pinfunction "2_2") (pintype "passive"))
      (node (ref "C51") (pin "2") (pinfunction "2_2") (pintype "passive"))
      (node (ref "C52") (pin "2") (pinfunction "2_2") (pintype "passive"))
      (node (ref "J6") (pin "1") (pinfunction "1_1") (pintype "bidirectional"))
      (node (ref "J7") (pin "1") (pinfunction "1_1") (pintype "bidirectional"))
      (node (ref "J8") (pin "1") (pinfunction "1_1") (pintype "bidirectional"))
      (node (ref "R20") (pin "1") (pinfunction "1_1") (pintype "passive"))
      (node (ref "R35") (pin "1") (pinfunction "1_1") (pintype "passive"))
      (node (ref "R38") (pin "1") (pinfunction "1_1") (pintype "passive"))
      (node (ref "U12") (pin "3") (pinfunction "OUT-_3") (pintype "bidirectional"))
      (node (ref "U13") (pin "2") (pinfunction "V-_2") (pintype "bidirectional"))
      (node (ref "U16") (pin "10") (pinfunction "GND2_10") (pintype "bidirectional"))
      (node (ref "U16") (pin "15") (pinfunction "GND2_15") (pintype "bidirectional"))
      (node (ref "U16") (pin "9") (pinfunction "GND2_9") (pintype "bidirectional"))
      (node (ref "U17") (pin "3") (pinfunction "GND_3") (pintype "bidirectional"))
      (node (ref "U20") (pin "2") (pinfunction "GND_2") (pintype "bidirectional"))
      (node (ref "U21") (pin "11") (pinfunction "IND_11") (pintype "bidirectional"))
      (node (ref "U21") (pin "15") (pinfunction "GND2_15") (pintype "bidirectional"))
      (node (ref "U21") (pin "9") (pinfunction "GND2_9") (pintype "bidirectional"))
      (node (ref "U23") (pin "5") (pinfunction "GND2_5") (pintype "bidirectional"))
    )
    (net (code "15") (name "/MOTOR_POWER_GND") (class "Default")
      (node (ref "C18") (pin "2") (pinfunction "2_2") (pintype "passive"))
      (node (ref "J9") (pin "1A") (pinfunction "1_1A") (pintype "bidirectional"))
      (node (ref "J9") (pin "1B") (pinfunction "1_1B") (pintype "bidirectional"))
      (node (ref "R14") (pin "1") (pinfunction "1_1") (pintype "passive"))
      (node (ref "U3") (pin "3") (pinfunction "VINN_3") (pintype "bidirectional"))
      (node (ref "U7") (pin "2") (pinfunction "B_2") (pintype "bidirectional"))
    )
    (net (code "16") (name "/MOTOR_POWER_IN") (class "Default")
      (node (ref "J9") (pin "2A") (pinfunction "2_2A") (pintype "bidirectional"))
      (node (ref "J9") (pin "2B") (pinfunction "2_2B") (pintype "bidirectional"))
      (node (ref "U2") (pin "5") (pinfunction "IP+_5") (pintype "bidirectional"))
    )
    (net (code "17") (name "/MOTOR_POWER_OUT") (class "Default")
      (node (ref "J9") (pin "3A") (pinfunction "3_3A") (pintype "bidirectional"))
      (node (ref "J9") (pin "3B") (pinfunction "3_3B") (pintype "bidirectional"))
      (node (ref "R13") (pin "2") (pinfunction "2_2") (pintype "passive"))
      (node (ref "U2") (pin "6") (pinfunction "IP-_6") (pintype "bidirectional"))
    )
    (net (code "18") (name "/PA0_FAN_PWM") (class "Default")
      (node (ref "D1") (pin "1") (pinfunction "C_1") (pintype "passive"))
      (node (ref "J10") (pin "4") (pinfunction "4_4") (pintype "bidirectional"))
      (node (ref "U22") (pin "CN10_29") (pinfunction "D32/TIMER_C_PWM1_CN10_29") (pintype "bidirectional"))
    )
    (net (code "19") (name "/PA5_SPI1_SCK") (class "Default")
      (node (ref "U1") (pin "37") (pinfunction "SCLK_37") (pintype "bidirectional"))
      (node (ref "U22") (pin "CN7_10") (pinfunction "D13/SPI_A_SCK_CN7_10") (pintype "bidirectional"))
    )
    (net (code "20") (name "/PA6_SPI1_MISO") (class "Default")
      (node (ref "U1") (pin "36") (pinfunction "SDO_36") (pintype "bidirectional"))
      (node (ref "U22") (pin "CN7_12") (pinfunction "D12/SPI_A_MISO_CN7_12") (pintype "bidirectional"))
    )
    (net (code "21") (name "/PB3_FAN_TACH") (class "Default")
      (node (ref "D2") (pin "1") (pinfunction "C_1") (pintype "passive"))
      (node (ref "R29") (pin "2") (pinfunction "2_2") (pintype "passive"))
      (node (ref "R30") (pin "1") (pinfunction "1_1") (pintype "passive"))
      (node (ref "U22") (pin "CN7_15") (pinfunction "D23/I2S_B_CK/SPI_B_SCK_CN7_15") (pintype "bidirectional"))
    )
    (net (code "22") (name "/PB5_SPI1_MOSI") (class "Default")
      (node (ref "U1") (pin "1") (pinfunction "SDI_1") (pintype "bidirectional"))
      (node (ref "U22") (pin "CN7_13") (pinfunction "D22/I2S_B_SD/SPI_B_MOSI_CN7_13") (pintype "bidirectional"))
    )
    (net (code "23") (name "/PB10_SPI2_SCK") (class "Default")
      (node (ref "U21") (pin "4") (pinfunction "INB_4") (pintype "bidirectional"))
      (node (ref "U22") (pin "CN10_32") (pinfunction "D36/TIMER_C_PWM2_CN10_32") (pintype "bidirectional"))
    )
    (net (code "24") (name "/PB11_CW_CAL") (class "Default")
      (node (ref "U18") (pin "1") (pinfunction "A_1") (pintype "bidirectional"))
      (node (ref "U22") (pin "CN10_34") (pinfunction "D35/TIMER_C_PWM3_CN10_34") (pintype "bidirectional"))
    )
    (net (code "25") (name "/PB12_SPI1_CS_ADC") (class "Default")
      (node (ref "U1") (pin "38") (pinfunction "CS#_38") (pintype "bidirectional"))
      (node (ref "U22") (pin "CN7_7") (pinfunction "D19/I2S_A_WS_CN7_7") (pintype "bidirectional"))
    )
    (net (code "26") (name "/PB15_SPI2_MOSI") (class "Default")
      (node (ref "U21") (pin "5") (pinfunction "INC_5") (pintype "bidirectional"))
      (node (ref "U22") (pin "CN7_3") (pinfunction "D17/I2S_A_SD_CN7_3") (pintype "bidirectional"))
    )
    (net (code "27") (name "/PC6_TIM3_CH1") (class "Default")
      (node (ref "C6") (pin "1") (pinfunction "1_1") (pintype "passive"))
      (node (ref "R1") (pin "2") (pinfunction "2_2") (pintype "passive"))
      (node (ref "U22") (pin "CN7_1") (pinfunction "D16/I2S_A_MCK_CN7_1") (pintype "bidirectional"))
    )
    (net (code "28") (name "/PC7_TIM3_CH2") (class "Default")
      (node (ref "C7") (pin "1") (pinfunction "1_1") (pintype "passive"))
      (node (ref "R2") (pin "2") (pinfunction "2_2") (pintype "passive"))
      (node (ref "U22") (pin "CN7_11") (pinfunction "D21/I2S_B_MCK_CN7_11") (pintype "bidirectional"))
    )
    (net (code "29") (name "/PD0_CAN1_RX") (class "Default")
      (node (ref "U22") (pin "CN9_25") (pinfunction "D67/CAN_RX_CN9_25") (pintype "input"))
      (node (ref "U23") (pin "3") (pinfunction "RXD_3") (pintype "input"))
    )
    (net (code "30") (name "/PD1_CAN1_TX") (class "Default")
      (node (ref "U22") (pin "CN9_27") (pinfunction "D66/CAN_TX_CN9_27") (pintype "output"))
      (node (ref "U23") (pin "2") (pinfunction "TXD_2") (pintype "input"))
    )
    (net (code "31") (name "/PD4_USART2_DE") (class "Default")
      (node (ref "U16") (pin "4") (pinfunction "RE/_4") (pintype "input"))
      (node (ref "U16") (pin "5") (pinfunction "DE_5") (pintype "input"))
      (node (ref "U22") (pin "CN9_8") (pinfunction "D54/USART_B_RTS_CN9_8") (pintype "bidirectional"))
    )
    (net (code "32") (name "/PD5_USART2_TX") (class "Default")
      (node (ref "U16") (pin "6") (pinfunction "DI_6") (pintype "input"))
      (node (ref "U22") (pin "CN9_6") (pinfunction "D53/USART_B_TX_CN9_6") (pintype "bidirectional"))
    )
    (net (code "33") (name "/PD6_USART2_RX") (class "Default")
      (node (ref "R22") (pin "1") (pinfunction "1_1") (pintype "passive"))
      (node (ref "U16") (pin "3") (pinfunction "RO_3") (pintype "output"))
      (node (ref "U22") (pin "CN9_4") (pinfunction "D52/USART_B_RX_CN9_4") (pintype "bidirectional"))
    )
    (net (code "34") (name "/PD13_LED_GREEN") (class "Default")
      (node (ref "J4") (pin "1") (pinfunction "1_1") (pintype "bidirectional"))
      (node (ref "U22") (pin "CN10_19") (pinfunction "D28/IO_CN10_19") (pintype "bidirectional"))
    )
    (net (code "35") (name "/PE0_CCW_CAL") (class "Default")
      (node (ref "U19") (pin "1") (pinfunction "A_1") (pintype "bidirectional"))
      (node (ref "U22") (pin "CN10_33") (pinfunction "D34/TIMER_B_ETR_CN10_33") (pintype "bidirectional"))
    )
    (net (code "36") (name "/PE6_ADC_RST") (class "Default")
      (node (ref "U1") (pin "2") (pinfunction "RST/PD_2") (pintype "bidirectional"))
      (node (ref "U22") (pin "CN9_20") (pinfunction "D59/SAI_A_SD_CN9_20") (pintype "bidirectional"))
    )
    (net (code "37") (name "/PE7_LED_RED") (class "Default")
      (node (ref "J4") (pin "2") (pinfunction "2_2") (pintype "bidirectional"))
      (node (ref "U22") (pin "CN10_20") (pinfunction "D41/TIMER_A_ETR_CN10_20") (pintype "bidirectional"))
    )
    (net (code "38") (name "/PE8_USART6_DE") (class "Default")
      (node (ref "U15") (pin "4") (pinfunction "RE/_4") (pintype "input"))
      (node (ref "U15") (pin "5") (pinfunction "DE_5") (pintype "input"))
      (node (ref "U22") (pin "CN10_18") (pinfunction "D42/TIMER_A_PWM1N_CN10_18") (pintype "bidirectional"))
    )
    (net (code "39") (name "/PE9_TIM1_CH1") (class "Default")
      (node (ref "C9") (pin "1") (pinfunction "1_1") (pintype "passive"))
      (node (ref "R5") (pin "2") (pinfunction "2_2") (pintype "passive"))
      (node (ref "U22") (pin "CN10_4") (pinfunction "D6/TIMER_A_PWM1_CN10_4") (pintype "bidirectional"))
    )
    (net (code "40") (name "/PE11_TIM1_CH2") (class "Default")
      (node (ref "C10") (pin "1") (pinfunction "1_1") (pintype "passive"))
      (node (ref "R6") (pin "2") (pinfunction "2_2") (pintype "passive"))
      (node (ref "U22") (pin "CN10_6") (pinfunction "D5/TIMER_A_PWM2_CN10_6") (pintype "bidirectional"))
    )
    (net (code "41") (name "/PF10_SPI2_CS_ANA") (class "Default")
      (node (ref "U21") (pin "3") (pinfunction "INA_3") (pintype "bidirectional"))
      (node (ref "U22") (pin "CN9_11") (pinfunction "A5/ADC3_IN8/I2C1_SCL_CN9_11") (pintype "input"))
    )
    (net (code "42") (name "/PG9_USART6_RX") (class "Default")
      (node (ref "R18") (pin "2") (pinfunction "2_2") (pintype "passive"))
      (node (ref "U15") (pin "3") (pinfunction "RO_3") (pintype "output"))
      (node (ref "U22") (pin "CN10_16") (pinfunction "D0/USART_A_RX_CN10_16") (pintype "input"))
    )
    (net (code "43") (name "/PG14_USART6_TX") (class "Default")
      (node (ref "U15") (pin "6") (pinfunction "DI_6") (pintype "input"))
      (node (ref "U22") (pin "CN10_14") (pinfunction "D1/USART_A_TX_CN10_14") (pintype "output"))
    )
    (net (code "44") (name "/TORQUE_ANALOG") (class "Default")
      (node (ref "J1") (pin "5") (pinfunction "5_5") (pintype "bidirectional"))
      (node (ref "R27") (pin "1") (pinfunction "1_1") (pintype "passive"))
      (node (ref "U8") (pin "1") (pinfunction "A_1") (pintype "bidirectional"))
    )
    (net (code "45") (name "/TORQUE_GROUND") (class "Default")
      (node (ref "J1") (pin "4") (pinfunction "4_4") (pintype "bidirectional"))
      (node (ref "R28") (pin "1") (pinfunction "1_1") (pintype "passive"))
      (node (ref "U18") (pin "3") (pinfunction "EMIT_3") (pintype "bidirectional"))
      (node (ref "U19") (pin "3") (pinfunction "EMIT_3") (pintype "bidirectional"))
      (node (ref "U8") (pin "2") (pinfunction "B_2") (pintype "bidirectional"))
    )
    (net (code "46") (name "/VIN_CN8") (class "Default")
      (node (ref "U22") (pin "CN8_15") (pinfunction "VIN_CN8_CN8_15") (pintype "power_in"))
    )
    (net (code "47") (name "GND") (class "Default")
      (node (ref "C1") (pin "2") (pinfunction "2_2") (pintype "passive"))
      (node (ref "C10") (pin "2") (pinfunction "2_2") (pintype "passive"))
      (node (ref "C11") (pin "2") (pinfunction "2_2") (pintype "passive"))
      (node (ref "C12") (pin "2") (pinfunction "2_2") (pintype "passive"))
      (node (ref "C13") (pin "2") (pinfunction "2_2") (pintype "passive"))
      (node (ref "C15") (pin "2") (pinfunction "2_2") (pintype "passive"))
      (node (ref "C19") (pin "2") (pinfunction "2_2") (pintype "passive"))
      (node (ref "C2") (pin "2") (pinfunction "2_2") (pintype "passive"))
      (node (ref "C20") (pin "2") (pinfunction "2_2") (pintype "passive"))
      (node (ref "C22") (pin "2") (pinfunction "2_2") (pintype "passive"))
      (node (ref "C25") (pin "2") (pinfunction "2_2") (pintype "passive"))
      (node (ref "C26") (pin "2") (pinfunction "-_2") (pintype "passive"))
      (node (ref "C27") (pin "2") (pinfunction "2_2") (pintype "passive"))
      (node (ref "C28") (pin "2") (pinfunction "2_2") (pintype "passive"))
      (node (ref "C29") (pin "2") (pinfunction "2_2") (pintype "passive"))
      (node (ref "C3") (pin "2") (pinfunction "2_2") (pintype "passive"))
      (node (ref "C31") (pin "2") (pinfunction "2_2") (pintype "passive"))
      (node (ref "C32") (pin "2") (pinfunction "2_2") (pintype "passive"))
      (node (ref "C33") (pin "2") (pinfunction "2_2") (pintype "passive"))
      (node (ref "C37") (pin "2") (pinfunction "2_2") (pintype "passive"))
      (node (ref "C38") (pin "2") (pinfunction "2_2") (pintype "passive"))
      (node (ref "C39") (pin "2") (pinfunction "2_2") (pintype "passive"))
      (node (ref "C4") (pin "2") (pinfunction "2_2") (pintype "passive"))
      (node (ref "C40") (pin "2") (pinfunction "2_2") (pintype "passive"))
      (node (ref "C42") (pin "2") (pinfunction "2_2") (pintype "passive"))
      (node (ref "C43") (pin "2") (pinfunction "2_2") (pintype "passive"))
      (node (ref "C44") (pin "2") (pinfunction "2_2") (pintype "passive"))
      (node (ref "C45") (pin "2") (pinfunction "2_2") (pintype "passive"))
      (node (ref "C5") (pin "2") (pinfunction "2_2") (pintype "passive"))
      (node (ref "C6") (pin "2") (pinfunction "2_2") (pintype "passive"))
      (node (ref "C7") (pin "2") (pinfunction "2_2") (pintype "passive"))
      (node (ref "C8") (pin "2") (pinfunction "2_2") (pintype "passive"))
      (node (ref "C9") (pin "2") (pinfunction "2_2") (pintype "passive"))
      (node (ref "D1") (pin "2") (pinfunction "A_2") (pintype "passive"))
      (node (ref "D2") (pin "2") (pinfunction "A_2") (pintype "passive"))
      (node (ref "H1") (pin "B3,2") (pinfunction "MOUNT_B3,2") (pintype "passive"))
      (node (ref "H2") (pin "B3,2") (pinfunction "MOUNT_B3,2") (pintype "passive"))
      (node (ref "H3") (pin "B3,2") (pinfunction "MOUNT_B3,2") (pintype "passive"))
      (node (ref "H4") (pin "B3,2") (pinfunction "MOUNT_B3,2") (pintype "passive"))
      (node (ref "H5") (pin "B3,2") (pinfunction "MOUNT_B3,2") (pintype "passive"))
      (node (ref "H6") (pin "B3,2") (pinfunction "MOUNT_B3,2") (pintype "passive"))
      (node (ref "J1") (pin "1") (pinfunction "1_1") (pintype "bidirectional"))
      (node (ref "J10") (pin "1") (pinfunction "1_1") (pintype "bidirectional"))
      (node (ref "J2") (pin "1") (pinfunction "1_1") (pintype "bidirectional"))
      (node (ref "J3") (pin "1") (pinfunction "1_1") (pintype "bidirectional"))
      (node (ref "POWER") (pin "1") (pinfunction "1_1") (pintype "bidirectional"))
      (node (ref "R12") (pin "1") (pinfunction "1_1") (pintype "passive"))
      (node (ref "R26") (pin "1") (pinfunction "1_1") (pintype "passive"))
      (node (ref "R29") (pin "1") (pinfunction "1_1") (pintype "passive"))
      (node (ref "R33") (pin "1") (pinfunction "1_1") (pintype "passive"))
      (node (ref "R34") (pin "1") (pinfunction "1_1") (pintype "passive"))
      (node (ref "U1") (pin "11") (pinfunction "AUX_GND_11") (pintype "bidirectional"))
      (node (ref "U1") (pin "22") (pinfunction "AIN_3GND_22") (pintype "bidirectional"))
      (node (ref "U1") (pin "28") (pinfunction "AGND_28") (pintype "bidirectional"))
      (node (ref "U1") (pin "29") (pinfunction "AGND_29") (pintype "bidirectional"))
      (node (ref "U1") (pin "3") (pinfunction "DAISY_3") (pintype "bidirectional"))
      (node (ref "U1") (pin "31") (pinfunction "AGND_31") (pintype "bidirectional"))
      (node (ref "U1") (pin "32") (pinfunction "AGND_32") (pintype "bidirectional"))
      (node (ref "U1") (pin "33") (pinfunction "DGND_33") (pintype "bidirectional"))
      (node (ref "U1") (pin "4") (pinfunction "REFSEL_4") (pintype "bidirectional"))
      (node (ref "U1") (pin "6") (pinfunction "REFGND_6") (pintype "bidirectional"))
      (node (ref "U1") (pin "8") (pinfunction "AGND_8") (pintype "bidirectional"))
      (node (ref "U10") (pin "3") (pinfunction "GND_3") (pintype "bidirectional"))
      (node (ref "U12") (pin "1") (pinfunction "IN-_1") (pintype "bidirectional"))
      (node (ref "U14") (pin "2") (pinfunction "GND_2") (pintype "input"))
      (node (ref "U15") (pin "2") (pinfunction "GND1_2") (pintype "bidirectional"))
      (node (ref "U15") (pin "7") (pinfunction "GND1_7") (pintype "bidirectional"))
      (node (ref "U15") (pin "8") (pinfunction "GND1_8") (pintype "bidirectional"))
      (node (ref "U16") (pin "2") (pinfunction "GND1_2") (pintype "bidirectional"))
      (node (ref "U16") (pin "7") (pinfunction "GND1_7") (pintype "bidirectional"))
      (node (ref "U16") (pin "8") (pinfunction "GND1_8") (pintype "bidirectional"))
      (node (ref "U18") (pin "2") (pinfunction "C_2") (pintype "bidirectional"))
      (node (ref "U19") (pin "2") (pinfunction "C_2") (pintype "bidirectional"))
      (node (ref "U2") (pin "2") (pinfunction "GND_2") (pintype "bidirectional"))
      (node (ref "U2") (pin "4") (pinfunction "GND_4") (pintype "bidirectional"))
      (node (ref "U2") (pin "7") (pinfunction "GND_7") (pintype "bidirectional"))
      (node (ref "U21") (pin "2") (pinfunction "GND1_2") (pintype "bidirectional"))
      (node (ref "U21") (pin "7") (pinfunction "EN1_7") (pintype "bidirectional"))
      (node (ref "U21") (pin "8") (pinfunction "GND1_8") (pintype "bidirectional"))
      (node (ref "U22") (pin "CN10_17") (pinfunction "GND_CN10_CN10_17") (pintype "power_in"))
      (node (ref "U22") (pin "CN10_22") (pinfunction "GND_CN10_CN10_22") (pintype "power_in"))
      (node (ref "U22") (pin "CN10_27") (pinfunction "GND_CN10_CN10_27") (pintype "power_in"))
      (node (ref "U22") (pin "CN10_3") (pinfunction "AGND_CN10_CN10_3") (pintype "power_in"))
      (node (ref "U22") (pin "CN10_5") (pinfunction "GND_CN10_CN10_5") (pintype "power_in"))
      (node (ref "U22") (pin "CN7_8") (pinfunction "GND_CN7_CN7_8") (pintype "power_in"))
      (node (ref "U22") (pin "CN8_11") (pinfunction "GND_CN8_CN8_11") (pintype "power_in"))
      (node (ref "U22") (pin "CN8_13") (pinfunction "GND_CN8_CN8_13") (pintype "power_in"))
      (node (ref "U22") (pin "CN9_12") (pinfunction "GND_CN9_CN9_12") (pintype "power_in"))
      (node (ref "U22") (pin "CN9_23") (pinfunction "GND_CN9_CN9_23") (pintype "power_in"))
      (node (ref "U23") (pin "4") (pinfunction "GND1_4") (pintype "bidirectional"))
      (node (ref "U24") (pin "15") (pinfunction "DCDC_GND_15") (pintype "bidirectional"))
      (node (ref "U24") (pin "9") (pinfunction "GND_9") (pintype "bidirectional"))
      (node (ref "U3") (pin "5") (pinfunction "GND2_5") (pintype "bidirectional"))
      (node (ref "U4") (pin "2") (pinfunction "V-_2") (pintype "bidirectional"))
      (node (ref "U5") (pin "1") (pinfunction "IN-_1") (pintype "bidirectional"))
      (node (ref "U6") (pin "1") (pinfunction "IN-_1") (pintype "bidirectional"))
      (node (ref "U8") (pin "3") (pinfunction "GND_3") (pintype "bidirectional"))
      (node (ref "U9") (pin "3") (pinfunction "GND_3") (pintype "bidirectional"))
    )
    (net (code "48") (name "Net-(J10-Pad3)") (class "Default")
      (node (ref "J10") (pin "3") (pinfunction "3_3") (pintype "bidirectional"))
      (node (ref "R30") (pin "2") (pinfunction "2_2") (pintype "passive"))
      (node (ref "R31") (pin "1") (pinfunction "1_1") (pintype "passive"))
    )
    (net (code "49") (name "Net-(T1-1)") (class "Default")
      (node (ref "C37") (pin "1") (pinfunction "1_1") (pintype "passive"))
      (node (ref "T1") (pin "T") (pinfunction "1_T") (pintype "bidirectional"))
      (node (ref "U1") (pin "23") (pinfunction "AIN_3P_23") (pintype "bidirectional"))
    )
    (net (code "50") (name "Net-(T2-1)") (class "Default")
      (node (ref "T2") (pin "T") (pinfunction "1_T") (pintype "bidirectional"))
      (node (ref "U1") (pin "10") (pinfunction "AUX_IN_10") (pintype "bidirectional"))
    )
    (net (code "51") (name "Net-(U1-AIN1_GND)") (class "Default")
      (node (ref "C34") (pin "2") (pinfunction "2_2") (pintype "passive"))
      (node (ref "R24") (pin "2") (pinfunction "2_2") (pintype "passive"))
      (node (ref "U1") (pin "19") (pinfunction "AIN1_GND_19") (pintype "bidirectional"))
    )
    (net (code "52") (name "Net-(U1-AIN_0GND)") (class "Default")
      (node (ref "C35") (pin "2") (pinfunction "2_2") (pintype "passive"))
      (node (ref "R26") (pin "2") (pinfunction "2_2") (pintype "passive"))
      (node (ref "U1") (pin "17") (pinfunction "AIN_0GND_17") (pintype "bidirectional"))
    )
    (net (code "53") (name "Net-(U1-AIN_0P)") (class "Default")
      (node (ref "C35") (pin "1") (pinfunction "1_1") (pintype "passive"))
      (node (ref "R25") (pin "2") (pinfunction "2_2") (pintype "passive"))
      (node (ref "U1") (pin "16") (pinfunction "AIN_0P_16") (pintype "bidirectional"))
    )
    (net (code "54") (name "Net-(U1-AIN_1P)") (class "Default")
      (node (ref "C34") (pin "1") (pinfunction "1_1") (pintype "passive"))
      (node (ref "R23") (pin "2") (pinfunction "2_2") (pintype "passive"))
      (node (ref "U1") (pin "18") (pinfunction "AIN_1P_18") (pintype "bidirectional"))
    )
    (net (code "55") (name "Net-(U1-AIN_2GND)") (class "Default")
      (node (ref "C36") (pin "2") (pinfunction "2_2") (pintype "passive"))
      (node (ref "R28") (pin "2") (pinfunction "2_2") (pintype "passive"))
      (node (ref "U1") (pin "20") (pinfunction "AIN_2GND_20") (pintype "bidirectional"))
    )
    (net (code "56") (name "Net-(U1-AIN_2P)") (class "Default")
      (node (ref "C36") (pin "1") (pinfunction "1_1") (pintype "passive"))
      (node (ref "R27") (pin "2") (pinfunction "2_2") (pintype "passive"))
      (node (ref "U1") (pin "21") (pinfunction "AIN_2P_21") (pintype "bidirectional"))
    )
    (net (code "57") (name "Net-(U1-REFCAP)") (class "Default")
      (node (ref "C27") (pin "1") (pinfunction "1_1") (pintype "passive"))
      (node (ref "C28") (pin "1") (pinfunction "1_1") (pintype "passive"))
      (node (ref "U1") (pin "7") (pinfunction "REFCAP_7") (pintype "bidirectional"))
    )
    (net (code "58") (name "Net-(U1-REFIO)") (class "Default")
      (node (ref "C29") (pin "1") (pinfunction "1_1") (pintype "passive"))
      (node (ref "U1") (pin "5") (pinfunction "REFIO_5") (pintype "bidirectional"))
    )
    (net (code "59") (name "Net-(U2-VOUT)") (class "Default")
      (node (ref "R23") (pin "1") (pinfunction "1_1") (pintype "passive"))
      (node (ref "U2") (pin "3") (pinfunction "VOUT_3") (pintype "bidirectional"))
      (node (ref "U24") (pin "11") (pinfunction "OUTP_11") (pintype "bidirectional"))
    )
    (net (code "60") (name "Net-(U3-GND1)") (class "Default")
      (node (ref "C14") (pin "2") (pinfunction "2_2") (pintype "passive"))
      (node (ref "C17") (pin "2") (pinfunction "2_2") (pintype "passive"))
      (node (ref "U3") (pin "4") (pinfunction "GND1_4") (pintype "bidirectional"))
      (node (ref "U5") (pin "3") (pinfunction "OUT-_3") (pintype "bidirectional"))
      (node (ref "U7") (pin "3") (pinfunction "GND_3") (pintype "bidirectional"))
    )
    (net (code "61") (name "Net-(U3-VDD1)") (class "Default")
      (node (ref "C14") (pin "1") (pinfunction "1_1") (pintype "passive"))
      (node (ref "C17") (pin "1") (pinfunction "1_1") (pintype "passive"))
      (node (ref "U3") (pin "1") (pinfunction "VDD1_1") (pintype "bidirectional"))
      (node (ref "U5") (pin "4") (pinfunction "OUT+_4") (pintype "bidirectional"))
    )
    (net (code "62") (name "Net-(U3-VINP)") (class "Default")
      (node (ref "C18") (pin "1") (pinfunction "1_1") (pintype "passive"))
      (node (ref "R13") (pin "1") (pinfunction "1_1") (pintype "passive"))
      (node (ref "R14") (pin "2") (pinfunction "2_2") (pintype "passive"))
      (node (ref "U3") (pin "2") (pinfunction "VINP_2") (pintype "bidirectional"))
      (node (ref "U7") (pin "1") (pinfunction "A_1") (pintype "bidirectional"))
    )
    (net (code "63") (name "Net-(U3-VOUTN)") (class "Default")
      (node (ref "R9") (pin "1") (pinfunction "1_1") (pintype "passive"))
      (node (ref "U3") (pin "6") (pinfunction "VOUTN_6") (pintype "bidirectional"))
    )
    (net (code "64") (name "Net-(U3-VOUTP)") (class "Default")
      (node (ref "R10") (pin "1") (pinfunction "1_1") (pintype "passive"))
      (node (ref "U3") (pin "7") (pinfunction "VOUTP_7") (pintype "bidirectional"))
    )
    (net (code "65") (name "Net-(U4-+)") (class "Default")
      (node (ref "R10") (pin "2") (pinfunction "2_2") (pintype "passive"))
      (node (ref "R12") (pin "2") (pinfunction "2_2") (pintype "passive"))
      (node (ref "U4") (pin "1") (pinfunction "+_1") (pintype "bidirectional"))
    )
    (net (code "66") (name "Net-(U4--)") (class "Default")
      (node (ref "R11") (pin "1") (pinfunction "1_1") (pintype "passive"))
      (node (ref "R9") (pin "2") (pinfunction "2_2") (pintype "passive"))
      (node (ref "U4") (pin "3") (pinfunction "-_3") (pintype "bidirectional"))
    )
    (net (code "67") (name "Net-(U4-OUT)") (class "Default")
      (node (ref "R11") (pin "2") (pinfunction "2_2") (pintype "passive"))
      (node (ref "R25") (pin "1") (pinfunction "1_1") (pintype "passive"))
      (node (ref "U4") (pin "4") (pinfunction "OUT_4") (pintype "bidirectional"))
    )
    (net (code "68") (name "Net-(U9-A)") (class "Default")
      (node (ref "J2") (pin "3") (pinfunction "3_3") (pintype "bidirectional"))
      (node (ref "R2") (pin "1") (pinfunction "1_1") (pintype "passive"))
      (node (ref "R4") (pin "1") (pinfunction "1_1") (pintype "passive"))
      (node (ref "U9") (pin "1") (pinfunction "A_1") (pintype "bidirectional"))
    )
    (net (code "69") (name "Net-(U9-B)") (class "Default")
      (node (ref "J2") (pin "4") (pinfunction "4_4") (pintype "bidirectional"))
      (node (ref "R1") (pin "1") (pinfunction "1_1") (pintype "passive"))
      (node (ref "R3") (pin "1") (pinfunction "1_1") (pintype "passive"))
      (node (ref "U9") (pin "2") (pinfunction "B_2") (pintype "bidirectional"))
    )
    (net (code "70") (name "Net-(U10-A)") (class "Default")
      (node (ref "J3") (pin "3") (pinfunction "3_3") (pintype "bidirectional"))
      (node (ref "R6") (pin "1") (pinfunction "1_1") (pintype "passive"))
      (node (ref "R8") (pin "1") (pinfunction "1_1") (pintype "passive"))
      (node (ref "U10") (pin "1") (pinfunction "A_1") (pintype "bidirectional"))
    )
    (net (code "71") (name "Net-(U10-B)") (class "Default")
      (node (ref "J3") (pin "4") (pinfunction "4_4") (pintype "bidirectional"))
      (node (ref "R5") (pin "1") (pinfunction "1_1") (pintype "passive"))
      (node (ref "R7") (pin "1") (pinfunction "1_1") (pintype "passive"))
      (node (ref "U10") (pin "2") (pinfunction "B_2") (pintype "bidirectional"))
    )
    (net (code "72") (name "Net-(U11-A)") (class "Default")
      (node (ref "J5") (pin "4") (pinfunction "4_4") (pintype "bidirectional"))
      (node (ref "R15") (pin "2") (pinfunction "2_2") (pintype "passive"))
      (node (ref "R16") (pin "1") (pinfunction "1_1") (pintype "passive"))
      (node (ref "U11") (pin "1") (pinfunction "A_1") (pintype "bidirectional"))
      (node (ref "U15") (pin "13") (pinfunction "B_13") (pintype "passive"))
    )
    (net (code "73") (name "Net-(U11-B)") (class "Default")
      (node (ref "J5") (pin "3") (pinfunction "3_3") (pintype "bidirectional"))
      (node (ref "R15") (pin "1") (pinfunction "1_1") (pintype "passive"))
      (node (ref "R17") (pin "2") (pinfunction "2_2") (pintype "passive"))
      (node (ref "U11") (pin "2") (pinfunction "B_2") (pintype "bidirectional"))
      (node (ref "U15") (pin "12") (pinfunction "A_12") (pintype "passive"))
    )
    (net (code "74") (name "Net-(U13-+)") (class "Default")
      (node (ref "R37") (pin "2") (pinfunction "2_2") (pintype "passive"))
      (node (ref "R38") (pin "2") (pinfunction "2_2") (pintype "passive"))
      (node (ref "U13") (pin "1") (pinfunction "+_1") (pintype "bidirectional"))
    )
    (net (code "75") (name "Net-(U13--)") (class "Default")
      (node (ref "R35") (pin "2") (pinfunction "2_2") (pintype "passive"))
      (node (ref "R36") (pin "1") (pinfunction "1_1") (pintype "passive"))
      (node (ref "U13") (pin "3") (pinfunction "-_3") (pintype "bidirectional"))
    )
    (net (code "76") (name "Net-(U20-DIN)") (class "Default")
      (node (ref "U20") (pin "4") (pinfunction "DIN_4") (pintype "bidirectional"))
      (node (ref "U21") (pin "12") (pinfunction "OUTC_12") (pintype "bidirectional"))
    )
    (net (code "77") (name "Net-(U20-SCLK)") (class "Default")
      (node (ref "U20") (pin "5") (pinfunction "SCLK_5") (pintype "bidirectional"))
      (node (ref "U21") (pin "13") (pinfunction "OUTB_13") (pintype "bidirectional"))
    )
    (net (code "78") (name "Net-(U20-SYNC)") (class "Default")
      (node (ref "U20") (pin "6") (pinfunction "SYNC_6") (pintype "bidirectional"))
      (node (ref "U21") (pin "14") (pinfunction "OUTA_14") (pintype "bidirectional"))
    )
    (net (code "79") (name "Net-(U20-VOUT)") (class "Default")
      (node (ref "R37") (pin "1") (pinfunction "1_1") (pintype "passive"))
      (node (ref "U20") (pin "1") (pinfunction "VOUT_1") (pintype "bidirectional"))
    )
    (net (code "80") (name "Net-(U23-CANH)") (class "Default")
      (node (ref "J8") (pin "3") (pinfunction "3_3") (pintype "bidirectional"))
      (node (ref "U23") (pin "7") (pinfunction "CANH_7") (pintype "passive"))
    )
    (net (code "81") (name "Net-(U23-CANL)") (class "Default")
      (node (ref "J8") (pin "2") (pinfunction "2_2") (pintype "bidirectional"))
      (node (ref "U23") (pin "6") (pinfunction "CANL_6") (pintype "passive"))
    )
    (net (code "82") (name "Net-(U24-DCDC_HGND)") (class "Default")
      (node (ref "C46") (pin "2") (pinfunction "2_2") (pintype "passive"))
      (node (ref "C47") (pin "2") (pinfunction "2_2") (pintype "passive"))
      (node (ref "C48") (pin "2") (pinfunction "2_2") (pintype "passive"))
      (node (ref "C49") (pin "1") (pinfunction "1_1") (pintype "passive"))
      (node (ref "C50") (pin "2") (pinfunction "2_2") (pintype "passive"))
      (node (ref "U24") (pin "2") (pinfunction "DCDC_HGND_2") (pintype "bidirectional"))
      (node (ref "U24") (pin "8") (pinfunction "HGND_8") (pintype "bidirectional"))
    )
    (net (code "83") (name "Net-(U24-DCDC_IN)") (class "Default")
      (node (ref "C43") (pin "1") (pinfunction "1_1") (pintype "passive"))
      (node (ref "U24") (pin "13") (pinfunction "LDO_OUT_13") (pintype "bidirectional"))
      (node (ref "U24") (pin "16") (pinfunction "DCDC_IN_16") (pintype "bidirectional"))
    )
    (net (code "84") (name "Net-(U24-DCDC_OUT)") (class "Default")
      (node (ref "C47") (pin "1") (pinfunction "1_1") (pintype "passive"))
      (node (ref "C48") (pin "1") (pinfunction "1_1") (pintype "passive"))
      (node (ref "U24") (pin "1") (pinfunction "DCDC_OUT_1") (pintype "bidirectional"))
    )
    (net (code "85") (name "Net-(U24-HDLO_IN)") (class "Default")
      (node (ref "C49") (pin "2") (pinfunction "2_2") (pintype "passive"))
      (node (ref "U24") (pin "3") (pinfunction "HDLO_IN_3") (pintype "bidirectional"))
    )
    (net (code "86") (name "Net-(U24-HDLO_OUT)") (class "Default")
      (node (ref "C46") (pin "1") (pinfunction "1_1") (pintype "passive"))
      (node (ref "C50") (pin "1") (pinfunction "1_1") (pintype "passive"))
      (node (ref "U24") (pin "5") (pinfunction "HDLO_OUT_5") (pintype "bidirectional"))
    )
    (net (code "87") (name "Net-(U24-OUTN)") (class "Default")
      (node (ref "R24") (pin "1") (pinfunction "1_1") (pintype "passive"))
      (node (ref "R34") (pin "2") (pinfunction "2_2") (pintype "passive"))
      (node (ref "U24") (pin "10") (pinfunction "OUTN_10") (pintype "bidirectional"))
    )
    (net (code "88") (name "VCC") (class "Default")
      (node (ref "C1") (pin "1") (pinfunction "1_1") (pintype "passive"))
      (node (ref "C19") (pin "1") (pinfunction "1_1") (pintype "passive"))
      (node (ref "C2") (pin "1") (pinfunction "1_1") (pintype "passive"))
      (node (ref "C22") (pin "1") (pinfunction "1_1") (pintype "passive"))
      (node (ref "C25") (pin "1") (pinfunction "1_1") (pintype "passive"))
      (node (ref "C31") (pin "1") (pinfunction "1_1") (pintype "passive"))
      (node (ref "C39") (pin "1") (pinfunction "1_1") (pintype "passive"))
      (node (ref "C4") (pin "1") (pinfunction "1_1") (pintype "passive"))
      (node (ref "C5") (pin "1") (pinfunction "1_1") (pintype "passive"))
      (node (ref "R18") (pin "1") (pinfunction "1_1") (pintype "passive"))
      (node (ref "R22") (pin "2") (pinfunction "2_2") (pintype "passive"))
      (node (ref "U1") (pin "34") (pinfunction "DVDD_34") (pintype "bidirectional"))
      (node (ref "U15") (pin "1") (pinfunction "VCC1_1") (pintype "bidirectional"))
      (node (ref "U16") (pin "1") (pinfunction "VCC1_1") (pintype "bidirectional"))
      (node (ref "U2") (pin "1") (pinfunction "VCC_1") (pintype "bidirectional"))
      (node (ref "U21") (pin "1") (pinfunction "VCC1_1") (pintype "bidirectional"))
      (node (ref "U22") (pin "CN8_7") (pinfunction "+3V3_CN8_CN8_7") (pintype "power_in"))
      (node (ref "U23") (pin "1") (pinfunction "VCC1_1") (pintype "bidirectional"))
      (node (ref "U3") (pin "8") (pinfunction "VDD2_8") (pintype "bidirectional"))
      (node (ref "U4") (pin "5") (pinfunction "V+_5") (pintype "bidirectional"))
    )
    (net (code "89") (name "unconnected-(J5-Pad2)") (class "Default")
      (node (ref "J5") (pin "2") (pinfunction "2_2") (pintype "bidirectional"))
    )
    (net (code "90") (name "unconnected-(J7-Pad2)") (class "Default")
      (node (ref "J7") (pin "2") (pinfunction "2_2") (pintype "bidirectional"))
    )
    (net (code "91") (name "unconnected-(U21-OUTD-Pad6)") (class "Default")
      (node (ref "U21") (pin "6") (pinfunction "OUTD_6") (pintype "bidirectional"))
    )
    (net (code "92") (name "unconnected-(U22A-D43{slash}SDMMC_D0-PadCN8_2)") (class "Default")
      (node (ref "U22") (pin "CN8_2") (pinfunction "D43/SDMMC_D0_CN8_2") (pintype "bidirectional"))
    )
    (net (code "93") (name "unconnected-(U22A-D44{slash}SDMMC_D1{slash}I2S_A_CKIN-PadCN8_4)") (class "Default")
      (node (ref "U22") (pin "CN8_4") (pinfunction "D44/SDMMC_D1/I2S_A_CKIN_CN8_4") (pintype "bidirectional"))
    )
    (net (code "94") (name "unconnected-(U22A-D45{slash}SDMMC_D2-PadCN8_6)") (class "Default")
      (node (ref "U22") (pin "CN8_6") (pinfunction "D45/SDMMC_D2_CN8_6") (pintype "bidirectional"))
    )
    (net (code "95") (name "unconnected-(U22A-D46{slash}SDMMC_D3-PadCN8_8)") (class "Default")
      (node (ref "U22") (pin "CN8_8") (pinfunction "D46/SDMMC_D3_CN8_8") (pintype "bidirectional"))
    )
    (net (code "96") (name "unconnected-(U22A-D47{slash}SDMMC_CK-PadCN8_10)") (class "Default")
      (node (ref "U22") (pin "CN8_10") (pinfunction "D47/SDMMC_CK_CN8_10") (pintype "bidirectional"))
    )
    (net (code "97") (name "unconnected-(U22A-D48{slash}SDMMC_CMD-PadCN8_12)") (class "Default")
      (node (ref "U22") (pin "CN8_12") (pinfunction "D48/SDMMC_CMD_CN8_12") (pintype "bidirectional"))
    )
    (net (code "98") (name "unconnected-(U22A-D49{slash}IO-PadCN8_14)") (class "Default")
      (node (ref "U22") (pin "CN8_14") (pinfunction "D49/IO_CN8_14") (pintype "bidirectional"))
    )
    (net (code "99") (name "unconnected-(U22A-D50{slash}IO-PadCN8_16)") (class "Default")
      (node (ref "U22") (pin "CN8_16") (pinfunction "D50/IO_CN8_16") (pintype "bidirectional"))
    )
    (net (code "100") (name "unconnected-(U22A-IOREF_CN8-PadCN8_3)") (class "Default")
      (node (ref "U22") (pin "CN8_3") (pinfunction "IOREF_CN8_CN8_3") (pintype "bidirectional"))
    )
    (net (code "101") (name "unconnected-(U22A-NC_CN8-PadCN8_1)") (class "Default")
      (node (ref "U22") (pin "CN8_1") (pinfunction "NC_CN8_CN8_1") (pintype "no_connect"))
    )
    (net (code "102") (name "unconnected-(U22A-RESET_CN8-PadCN8_5)") (class "Default")
      (node (ref "U22") (pin "CN8_5") (pinfunction "RESET_CN8_CN8_5") (pintype "bidirectional"))
    )
    (net (code "103") (name "unconnected-(U22B-A0{slash}ADC123_IN3-PadCN9_1)") (class "Default")
      (node (ref "U22") (pin "CN9_1") (pinfunction "A0/ADC123_IN3_CN9_1") (pintype "input"))
    )
    (net (code "104") (name "unconnected-(U22B-A1{slash}ADC123_IN10-PadCN9_3)") (class "Default")
      (node (ref "U22") (pin "CN9_3") (pinfunction "A1/ADC123_IN10_CN9_3") (pintype "input"))
    )
    (net (code "105") (name "unconnected-(U22B-A2{slash}ADC123_IN13-PadCN9_5)") (class "Default")
      (node (ref "U22") (pin "CN9_5") (pinfunction "A2/ADC123_IN13_CN9_5") (pintype "input"))
    )
    (net (code "106") (name "unconnected-(U22B-A3{slash}ADC3_IN9-PadCN9_7)") (class "Default")
      (node (ref "U22") (pin "CN9_7") (pinfunction "A3/ADC3_IN9_CN9_7") (pintype "input"))
    )
    (net (code "107") (name "unconnected-(U22B-A4{slash}ADC3_IN15{slash}I2C1_SDA-PadCN9_9)") (class "Default")
      (node (ref "U22") (pin "CN9_9") (pinfunction "A4/ADC3_IN15/I2C1_SDA_CN9_9") (pintype "input"))
    )
    (net (code "108") (name "unconnected-(U22B-D51{slash}USART_B_SCLK-PadCN9_2)") (class "Default")
      (node (ref "U22") (pin "CN9_2") (pinfunction "D51/USART_B_SCLK_CN9_2") (pintype "bidirectional"))
    )
    (net (code "109") (name "unconnected-(U22B-D55{slash}USART_B_CTS-PadCN9_10)") (class "Default")
      (node (ref "U22") (pin "CN9_10") (pinfunction "D55/USART_B_CTS_CN9_10") (pintype "bidirectional"))
    )
    (net (code "110") (name "unconnected-(U22B-D56{slash}SAI_A_MCLK-PadCN9_14)") (class "Default")
      (node (ref "U22") (pin "CN9_14") (pinfunction "D56/SAI_A_MCLK_CN9_14") (pintype "bidirectional"))
    )
    (net (code "111") (name "unconnected-(U22B-D57{slash}SAI_A_FS-PadCN9_16)") (class "Default")
      (node (ref "U22") (pin "CN9_16") (pinfunction "D57/SAI_A_FS_CN9_16") (pintype "bidirectional"))
    )
    (net (code "112") (name "unconnected-(U22B-D58{slash}SAI_A_SCK-PadCN9_18)") (class "Default")
      (node (ref "U22") (pin "CN9_18") (pinfunction "D58/SAI_A_SCK_CN9_18") (pintype "bidirectional"))
    )
    (net (code "113") (name "unconnected-(U22B-D60{slash}SAI_B_SD-PadCN9_22)") (class "Default")
      (node (ref "U22") (pin "CN9_22") (pinfunction "D60/SAI_B_SD_CN9_22") (pintype "bidirectional"))
    )
    (net (code "114") (name "unconnected-(U22B-D61{slash}SAI_B_SCK-PadCN9_24)") (class "Default")
      (node (ref "U22") (pin "CN9_24") (pinfunction "D61/SAI_B_SCK_CN9_24") (pintype "bidirectional"))
    )
    (net (code "115") (name "unconnected-(U22B-D62{slash}SAI_B_MCLK-PadCN9_26)") (class "Default")
      (node (ref "U22") (pin "CN9_26") (pinfunction "D62/SAI_B_MCLK_CN9_26") (pintype "bidirectional"))
    )
    (net (code "116") (name "unconnected-(U22B-D63{slash}SAI_B_FS-PadCN9_28)") (class "Default")
      (node (ref "U22") (pin "CN9_28") (pinfunction "D63/SAI_B_FS_CN9_28") (pintype "bidirectional"))
    )
    (net (code "117") (name "unconnected-(U22B-D64{slash}IO-PadCN9_30)") (class "Default")
      (node (ref "U22") (pin "CN9_30") (pinfunction "D64/IO_CN9_30") (pintype "bidirectional"))
    )
    (net (code "118") (name "unconnected-(U22B-D65{slash}IO-PadCN9_29)") (class "Default")
      (node (ref "U22") (pin "CN9_29") (pinfunction "D65/IO_CN9_29") (pintype "bidirectional"))
    )
    (net (code "119") (name "unconnected-(U22B-D68{slash}I2C_B_SDA-PadCN9_21)") (class "Default")
      (node (ref "U22") (pin "CN9_21") (pinfunction "D68/I2C_B_SDA_CN9_21") (pintype "bidirectional"))
    )
    (net (code "120") (name "unconnected-(U22B-D69{slash}I2C_B_SCL-PadCN9_19)") (class "Default")
      (node (ref "U22") (pin "CN9_19") (pinfunction "D69/I2C_B_SCL_CN9_19") (pintype "bidirectional"))
    )
    (net (code "121") (name "unconnected-(U22B-D70{slash}I2C_B_SMBA-PadCN9_17)") (class "Default")
      (node (ref "U22") (pin "CN9_17") (pinfunction "D70/I2C_B_SMBA_CN9_17") (pintype "bidirectional"))
    )
    (net (code "122") (name "unconnected-(U22B-D71{slash}IO-PadCN9_15)") (class "Default")
      (node (ref "U22") (pin "CN9_15") (pinfunction "D71/IO_CN9_15") (pintype "bidirectional"))
    )
    (net (code "123") (name "unconnected-(U22B-D72{slash}NC-PadCN9_13)") (class "Default")
      (node (ref "U22") (pin "CN9_13") (pinfunction "D72/NC_CN9_13") (pintype "bidirectional"))
    )
    (net (code "124") (name "unconnected-(U22C-D8{slash}IO-PadCN7_20)") (class "Default")
      (node (ref "U22") (pin "CN7_20") (pinfunction "D8/IO_CN7_20") (pintype "bidirectional"))
    )
    (net (code "125") (name "unconnected-(U22C-D9{slash}TIMER_B_PWM2-PadCN7_18)") (class "Default")
      (node (ref "U22") (pin "CN7_18") (pinfunction "D9/TIMER_B_PWM2_CN7_18") (pintype "bidirectional"))
    )
    (net (code "126") (name "unconnected-(U22C-D10{slash}SPI_A_CS{slash}TIM_B_PWM3-PadCN7_16)") (class "Default")
      (node (ref "U22") (pin "CN7_16") (pinfunction "D10/SPI_A_CS/TIM_B_PWM3_CN7_16") (pintype "bidirectional"))
    )
    (net (code "127") (name "unconnected-(U22C-D11{slash}SPI_A_MOSI{slash}TIM_E_PWM1-PadCN7_14)") (class "Default")
      (node (ref "U22") (pin "CN7_14") (pinfunction "D11/SPI_A_MOSI/TIM_E_PWM1_CN7_14") (pintype "bidirectional"))
    )
    (net (code "128") (name "unconnected-(U22C-D14{slash}I2C_A_SDA-PadCN7_4)") (class "Default")
      (node (ref "U22") (pin "CN7_4") (pinfunction "D14/I2C_A_SDA_CN7_4") (pintype "bidirectional"))
    )
    (net (code "129") (name "unconnected-(U22C-D15{slash}I2C_A_SCL-PadCN7_2)") (class "Default")
      (node (ref "U22") (pin "CN7_2") (pinfunction "D15/I2C_A_SCL_CN7_2") (pintype "bidirectional"))
    )
    (net (code "130") (name "unconnected-(U22C-D18{slash}I2S_A_CK-PadCN7_5)") (class "Default")
      (node (ref "U22") (pin "CN7_5") (pinfunction "D18/I2S_A_CK_CN7_5") (pintype "bidirectional"))
    )
    (net (code "131") (name "unconnected-(U22C-D20{slash}I2S_B_WS-PadCN7_9)") (class "Default")
      (node (ref "U22") (pin "CN7_9") (pinfunction "D20/I2S_B_WS_CN7_9") (pintype "bidirectional"))
    )
    (net (code "132") (name "unconnected-(U22C-D25{slash}SPI_B_MISO-PadCN7_19)") (class "Default")
      (node (ref "U22") (pin "CN7_19") (pinfunction "D25/SPI_B_MISO_CN7_19") (pintype "bidirectional"))
    )
    (net (code "133") (name "unconnected-(U22D-A6{slash}ADC_A_IN-PadCN10_7)") (class "Default")
      (node (ref "U22") (pin "CN10_7") (pinfunction "A6/ADC_A_IN_CN10_7") (pintype "input"))
    )
    (net (code "134") (name "unconnected-(U22D-A7{slash}ADC_B_IN-PadCN10_9)") (class "Default")
      (node (ref "U22") (pin "CN10_9") (pinfunction "A7/ADC_B_IN_CN10_9") (pintype "input"))
    )
    (net (code "135") (name "unconnected-(U22D-A8{slash}ADC_C_IN-PadCN10_11)") (class "Default")
      (node (ref "U22") (pin "CN10_11") (pinfunction "A8/ADC_C_IN_CN10_11") (pintype "input"))
    )
    (net (code "136") (name "unconnected-(U22D-D2{slash}IO-PadCN10_12)") (class "Default")
      (node (ref "U22") (pin "CN10_12") (pinfunction "D2/IO_CN10_12") (pintype "bidirectional"))
    )
    (net (code "137") (name "unconnected-(U22D-D3{slash}TIMER_A_PWM3-PadCN10_10)") (class "Default")
      (node (ref "U22") (pin "CN10_10") (pinfunction "D3/TIMER_A_PWM3_CN10_10") (pintype "bidirectional"))
    )
    (net (code "138") (name "unconnected-(U22D-D4{slash}IO-PadCN10_8)") (class "Default")
      (node (ref "U22") (pin "CN10_8") (pinfunction "D4/IO_CN10_8") (pintype "bidirectional"))
    )
    (net (code "139") (name "unconnected-(U22D-D7{slash}IO-PadCN10_2)") (class "Default")
      (node (ref "U22") (pin "CN10_2") (pinfunction "D7/IO_CN10_2") (pintype "bidirectional"))
    )
    (net (code "140") (name "unconnected-(U22D-D26{slash}IO-PadCN10_13)") (class "Default")
      (node (ref "U22") (pin "CN10_13") (pinfunction "D26/IO_CN10_13") (pintype "bidirectional"))
    )
    (net (code "141") (name "unconnected-(U22D-D27{slash}IO-PadCN10_15)") (class "Default")
      (node (ref "U22") (pin "CN10_15") (pinfunction "D27/IO_CN10_15") (pintype "bidirectional"))
    )
    (net (code "142") (name "unconnected-(U22D-D29{slash}IO-PadCN10_21)") (class "Default")
      (node (ref "U22") (pin "CN10_21") (pinfunction "D29/IO_CN10_21") (pintype "bidirectional"))
    )
    (net (code "143") (name "unconnected-(U22D-D30{slash}IO-PadCN10_23)") (class "Default")
      (node (ref "U22") (pin "CN10_23") (pinfunction "D30/IO_CN10_23") (pintype "bidirectional"))
    )
    (net (code "144") (name "unconnected-(U22D-D31{slash}IO-PadCN10_25)") (class "Default")
      (node (ref "U22") (pin "CN10_25") (pinfunction "D31/IO_CN10_25") (pintype "bidirectional"))
    )
    (net (code "145") (name "unconnected-(U22D-D33{slash}TIMER_D_PWM1-PadCN10_31)") (class "Default")
      (node (ref "U22") (pin "CN10_31") (pinfunction "D33/TIMER_D_PWM1_CN10_31") (pintype "bidirectional"))
    )
    (net (code "146") (name "unconnected-(U22D-D37{slash}TIMER_A_BKIN1-PadCN10_30)") (class "Default")
      (node (ref "U22") (pin "CN10_30") (pinfunction "D37/TIMER_A_BKIN1_CN10_30") (pintype "bidirectional"))
    )
    (net (code "147") (name "unconnected-(U22D-D38{slash}IO-PadCN10_28)") (class "Default")
      (node (ref "U22") (pin "CN10_28") (pinfunction "D38/IO_CN10_28") (pintype "bidirectional"))
    )
    (net (code "148") (name "unconnected-(U22D-D39{slash}TIMER_A_PWM3N-PadCN10_26)") (class "Default")
      (node (ref "U22") (pin "CN10_26") (pinfunction "D39/TIMER_A_PWM3N_CN10_26") (pintype "bidirectional"))
    )
    (net (code "149") (name "unconnected-(U22D-D40{slash}TIMER_A_PWM2N-PadCN10_24)") (class "Default")
      (node (ref "U22") (pin "CN10_24") (pinfunction "D40/TIMER_A_PWM2N_CN10_24") (pintype "bidirectional"))
    )
    (net (code "150") (name "unconnected-(U24-DIAG-Pad14)") (class "Default")
      (node (ref "U24") (pin "14") (pinfunction "DIAG_14") (pintype "bidirectional"))
    )
    (net (code "151") (name "unconnected-(U24-INN-Pad7)") (class "Default")
      (node (ref "U24") (pin "7") (pinfunction "INN_7") (pintype "bidirectional"))
    )
    (net (code "152") (name "unconnected-(U24-INP-Pad6)") (class "Default")
      (node (ref "U24") (pin "6") (pinfunction "INP_6") (pintype "bidirectional"))
    )
  )
)
